# SM3320-BATT-EV.net
KiCad netlist of a schematic drawn in Altium Designer
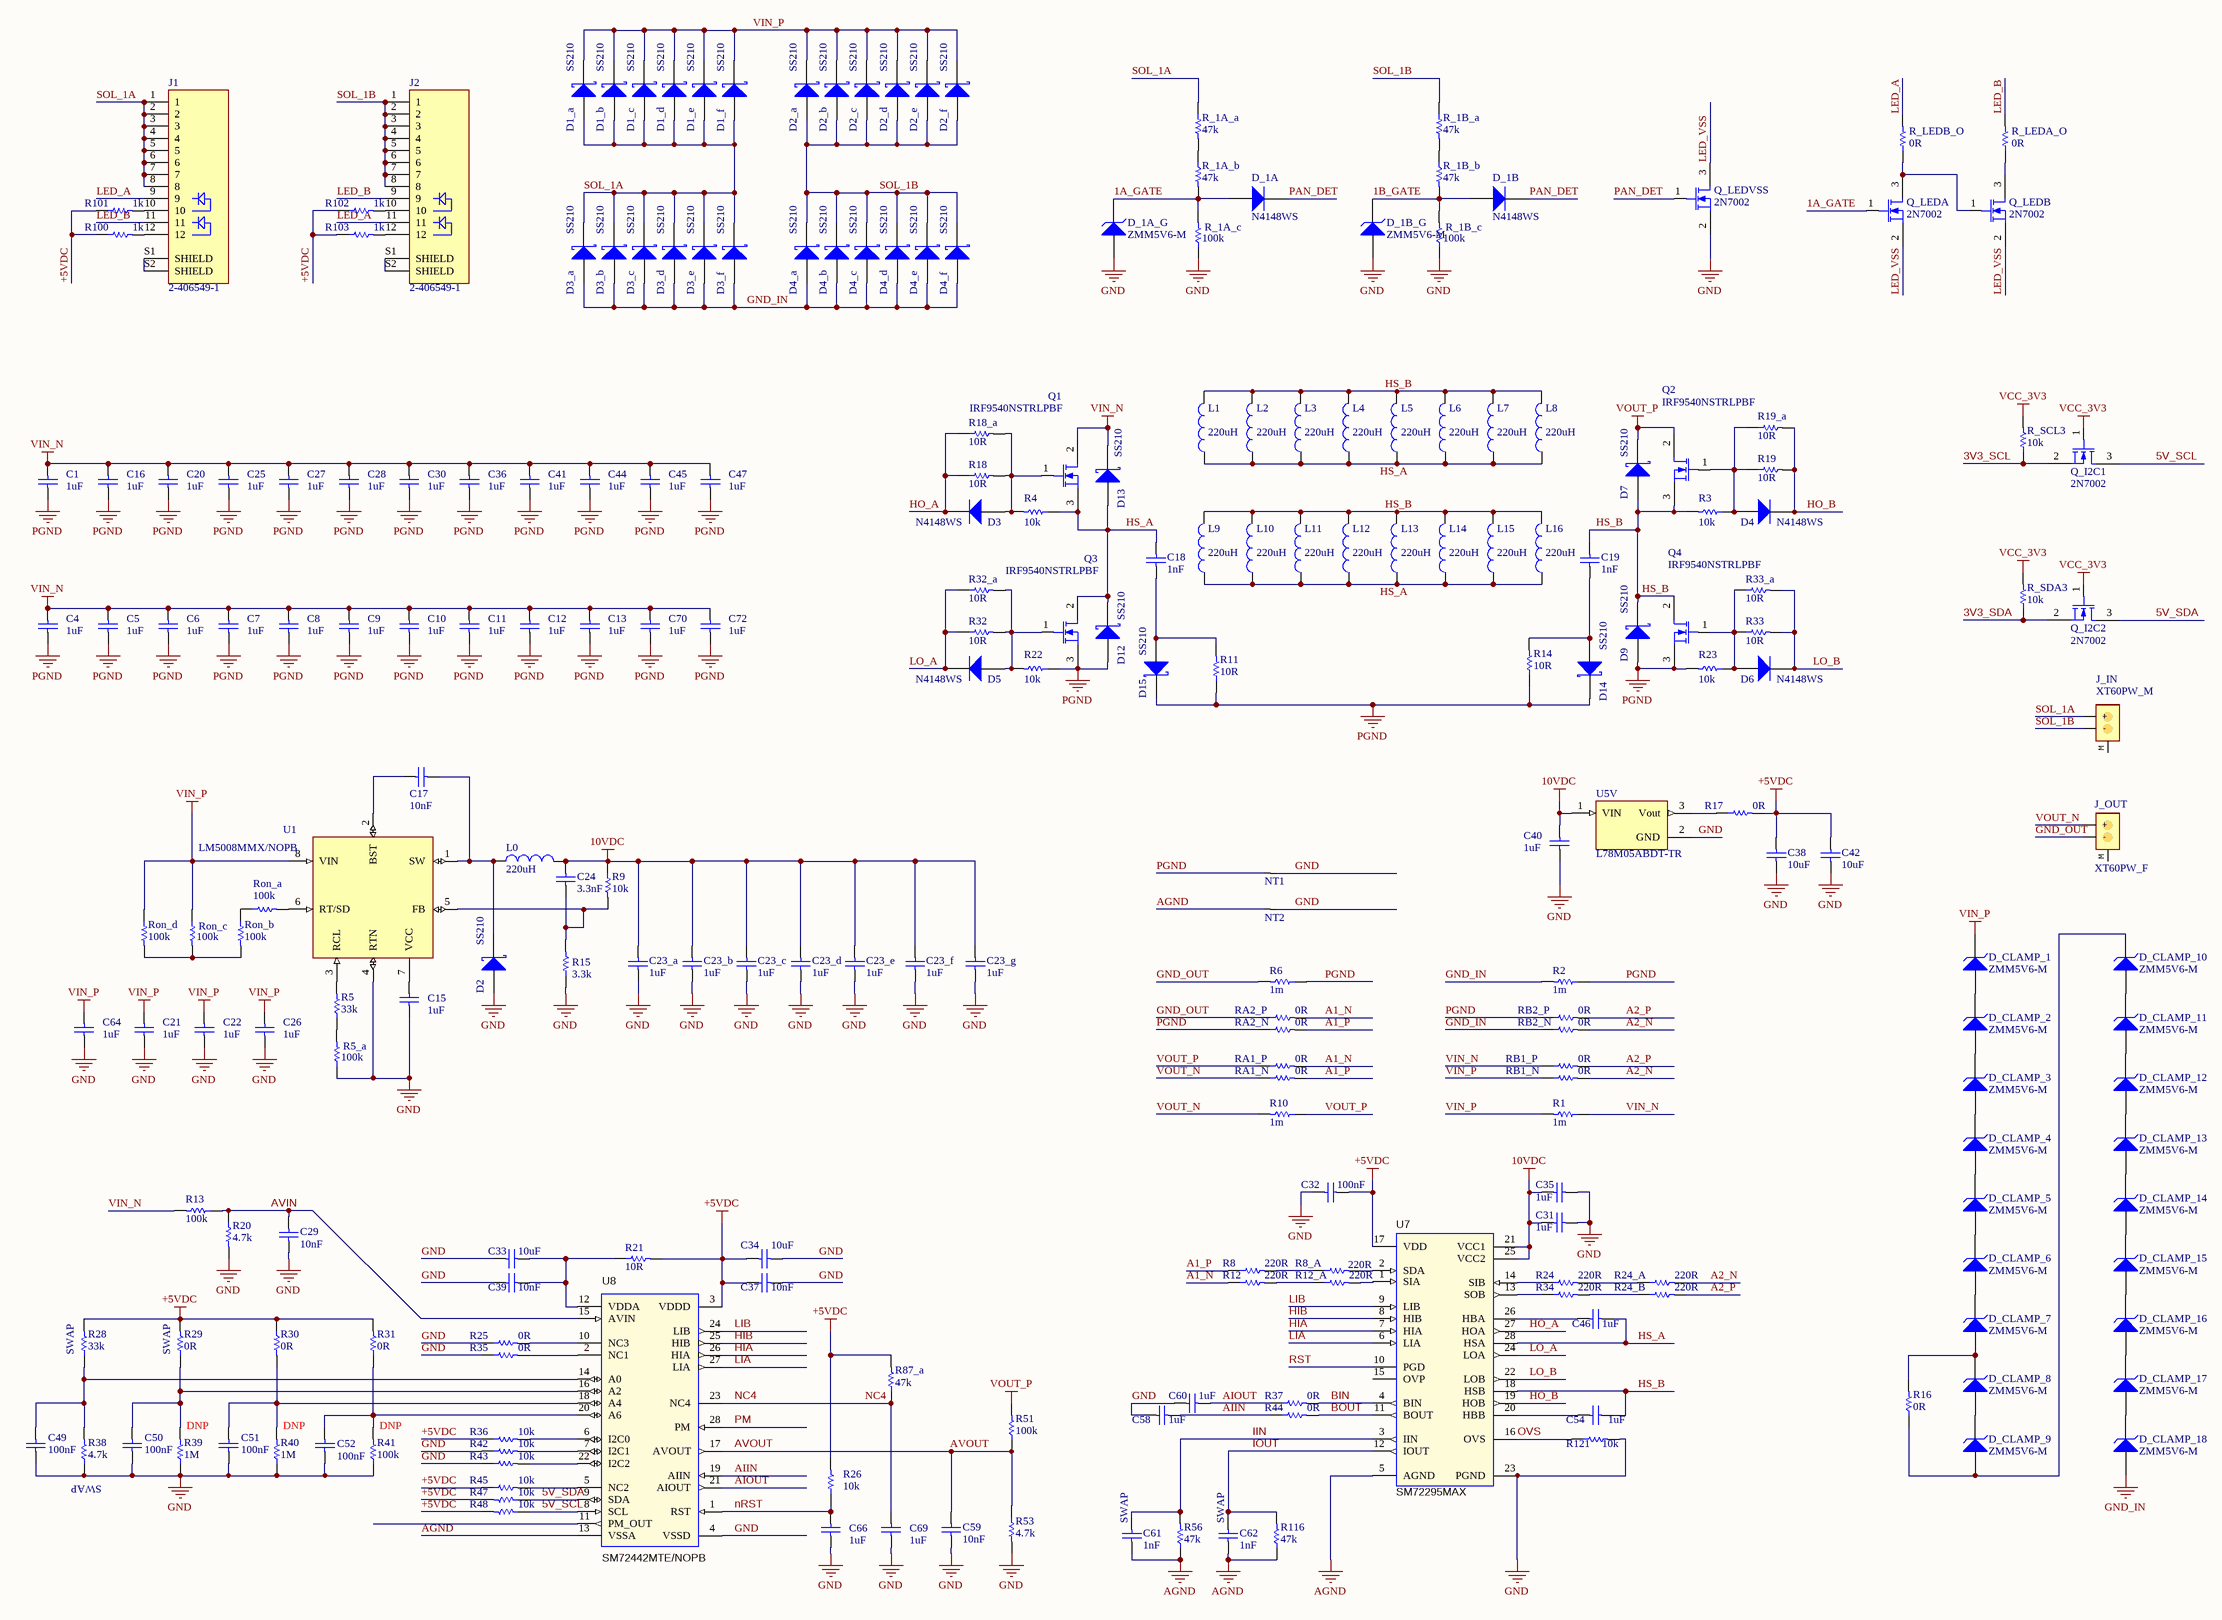
[diagram p0: SM3320-BATT-EV.SchDoc]

(export (version "E")
  (design (tool "Eeschema 10.0.6"))
  (components
    (comp (ref "C1")
      (value "1uF")
      (footprint "C_1206")
      (description "C - CAPACITOR - MLCC - 1uF - 100V - 1206 - X7R")
      (fields (field (name "LCSC PART #") "C91151") (field (name "Comment") "1206B105K101NT"))
      (libsource (lib "JLC_PCB") (part "1206B105K101NT"))
    )
    (comp (ref "C4")
      (value "1uF")
      (footprint "C_1206")
      (description "C - CAPACITOR - MLCC - 1uF - 100V - 1206 - X7R")
      (fields (field (name "LCSC PART #") "C91151") (field (name "Comment") "1206B105K101NT"))
      (libsource (lib "JLC_PCB") (part "1206B105K101NT"))
    )
    (comp (ref "C5")
      (value "1uF")
      (footprint "C_1206")
      (description "C - CAPACITOR - MLCC - 1uF - 100V - 1206 - X7R")
      (fields (field (name "LCSC PART #") "C91151") (field (name "Comment") "1206B105K101NT"))
      (libsource (lib "JLC_PCB") (part "1206B105K101NT"))
    )
    (comp (ref "C6")
      (value "1uF")
      (footprint "C_1206")
      (description "C - CAPACITOR - MLCC - 1uF - 100V - 1206 - X7R")
      (fields (field (name "LCSC PART #") "C91151") (field (name "Comment") "1206B105K101NT"))
      (libsource (lib "JLC_PCB") (part "1206B105K101NT"))
    )
    (comp (ref "C7")
      (value "1uF")
      (footprint "C_1206")
      (description "C - CAPACITOR - MLCC - 1uF - 100V - 1206 - X7R")
      (fields (field (name "LCSC PART #") "C91151") (field (name "Comment") "1206B105K101NT"))
      (libsource (lib "JLC_PCB") (part "1206B105K101NT"))
    )
    (comp (ref "C8")
      (value "1uF")
      (footprint "C_1206")
      (description "C - CAPACITOR - MLCC - 1uF - 100V - 1206 - X7R")
      (fields (field (name "LCSC PART #") "C91151") (field (name "Comment") "1206B105K101NT"))
      (libsource (lib "JLC_PCB") (part "1206B105K101NT"))
    )
    (comp (ref "C9")
      (value "1uF")
      (footprint "C_1206")
      (description "C - CAPACITOR - MLCC - 1uF - 100V - 1206 - X7R")
      (fields (field (name "LCSC PART #") "C91151") (field (name "Comment") "1206B105K101NT"))
      (libsource (lib "JLC_PCB") (part "1206B105K101NT"))
    )
    (comp (ref "C10")
      (value "1uF")
      (footprint "C_1206")
      (description "C - CAPACITOR - MLCC - 1uF - 100V - 1206 - X7R")
      (fields (field (name "LCSC PART #") "C91151") (field (name "Comment") "1206B105K101NT"))
      (libsource (lib "JLC_PCB") (part "1206B105K101NT"))
    )
    (comp (ref "C11")
      (value "1uF")
      (footprint "C_1206")
      (description "C - CAPACITOR - MLCC - 1uF - 100V - 1206 - X7R")
      (fields (field (name "LCSC PART #") "C91151") (field (name "Comment") "1206B105K101NT"))
      (libsource (lib "JLC_PCB") (part "1206B105K101NT"))
    )
    (comp (ref "C12")
      (value "1uF")
      (footprint "C_1206")
      (description "C - CAPACITOR - MLCC - 1uF - 100V - 1206 - X7R")
      (fields (field (name "LCSC PART #") "C91151") (field (name "Comment") "1206B105K101NT"))
      (libsource (lib "JLC_PCB") (part "1206B105K101NT"))
    )
    (comp (ref "C13")
      (value "1uF")
      (footprint "C_1206")
      (description "C - CAPACITOR - MLCC - 1uF - 100V - 1206 - X7R")
      (fields (field (name "LCSC PART #") "C91151") (field (name "Comment") "1206B105K101NT"))
      (libsource (lib "JLC_PCB") (part "1206B105K101NT"))
    )
    (comp (ref "C15")
      (value "1uF")
      (footprint "C_0402")
      (description "C - CAPACITOR - MLCC - 1uF - 25V - 0402")
      (fields (field (name "LCSC PART #") "C52923") (field (name "Comment") "CL05A105KA5NQNC"))
      (libsource (lib "JLC_PCB") (part "CL05A105KA5NQNC"))
    )
    (comp (ref "C16")
      (value "1uF")
      (footprint "C_1206")
      (description "C - CAPACITOR - MLCC - 1uF - 100V - 1206 - X7R")
      (fields (field (name "LCSC PART #") "C91151") (field (name "Comment") "1206B105K101NT"))
      (libsource (lib "JLC_PCB") (part "1206B105K101NT"))
    )
    (comp (ref "C17")
      (value "10nF")
      (footprint "C_0402")
      (description "C - CAPACITOR - MLCC - 10nF - 50V - 0402")
      (fields (field (name "LCSC PART #") "C15195") (field (name "Comment") "CL05B103KB5NNNC"))
      (libsource (lib "JLC_PCB") (part "CL05B103KB5NNNC"))
    )
    (comp (ref "C18")
      (value "1nF")
      (footprint "C_1206")
      (description "C - CAPACITOR - MLCC - 1nF - 2000V - 1206 - X7R")
      (fields (field (name "LCSC PART #") "C9196") (field (name "Comment") "1206B102K202NT"))
      (libsource (lib "JLC_PCB") (part "1206B102K202NT"))
    )
    (comp (ref "C19")
      (value "1nF")
      (footprint "C_1206")
      (description "C - CAPACITOR - MLCC - 1nF - 2000V - 1206 - X7R")
      (fields (field (name "LCSC PART #") "C9196") (field (name "Comment") "1206B102K202NT"))
      (libsource (lib "JLC_PCB") (part "1206B102K202NT"))
    )
    (comp (ref "C20")
      (value "1uF")
      (footprint "C_1206")
      (description "C - CAPACITOR - MLCC - 1uF - 100V - 1206 - X7R")
      (fields (field (name "LCSC PART #") "C91151") (field (name "Comment") "1206B105K101NT"))
      (libsource (lib "JLC_PCB") (part "1206B105K101NT"))
    )
    (comp (ref "C21")
      (value "1uF")
      (footprint "C_1206")
      (description "C - CAPACITOR - MLCC - 1uF - 100V - 1206 - X7R")
      (fields (field (name "LCSC PART #") "C91151") (field (name "Comment") "1206B105K101NT"))
      (libsource (lib "JLC_PCB") (part "1206B105K101NT"))
    )
    (comp (ref "C22")
      (value "1uF")
      (footprint "C_1206")
      (description "C - CAPACITOR - MLCC - 1uF - 100V - 1206 - X7R")
      (fields (field (name "LCSC PART #") "C91151") (field (name "Comment") "1206B105K101NT"))
      (libsource (lib "JLC_PCB") (part "1206B105K101NT"))
    )
    (comp (ref "C23_a")
      (value "1uF")
      (footprint "C_0402")
      (description "C - CAPACITOR - MLCC - 1uF - 25V - 0402")
      (fields (field (name "LCSC PART #") "C52923") (field (name "Comment") "CL05A105KA5NQNC"))
      (libsource (lib "JLC_PCB") (part "CL05A105KA5NQNC"))
    )
    (comp (ref "C23_b")
      (value "1uF")
      (footprint "C_0402")
      (description "C - CAPACITOR - MLCC - 1uF - 25V - 0402")
      (fields (field (name "LCSC PART #") "C52923") (field (name "Comment") "CL05A105KA5NQNC"))
      (libsource (lib "JLC_PCB") (part "CL05A105KA5NQNC"))
    )
    (comp (ref "C23_c")
      (value "1uF")
      (footprint "C_0402")
      (description "C - CAPACITOR - MLCC - 1uF - 25V - 0402")
      (fields (field (name "LCSC PART #") "C52923") (field (name "Comment") "CL05A105KA5NQNC"))
      (libsource (lib "JLC_PCB") (part "CL05A105KA5NQNC"))
    )
    (comp (ref "C23_d")
      (value "1uF")
      (footprint "C_0402")
      (description "C - CAPACITOR - MLCC - 1uF - 25V - 0402")
      (fields (field (name "LCSC PART #") "C52923") (field (name "Comment") "CL05A105KA5NQNC"))
      (libsource (lib "JLC_PCB") (part "CL05A105KA5NQNC"))
    )
    (comp (ref "C23_e")
      (value "1uF")
      (footprint "C_0402")
      (description "C - CAPACITOR - MLCC - 1uF - 25V - 0402")
      (fields (field (name "LCSC PART #") "C52923") (field (name "Comment") "CL05A105KA5NQNC"))
      (libsource (lib "JLC_PCB") (part "CL05A105KA5NQNC"))
    )
    (comp (ref "C23_f")
      (value "1uF")
      (footprint "C_0402")
      (description "C - CAPACITOR - MLCC - 1uF - 25V - 0402")
      (fields (field (name "LCSC PART #") "C52923") (field (name "Comment") "CL05A105KA5NQNC"))
      (libsource (lib "JLC_PCB") (part "CL05A105KA5NQNC"))
    )
    (comp (ref "C23_g")
      (value "1uF")
      (footprint "C_0402")
      (description "C - CAPACITOR - MLCC - 1uF - 25V - 0402")
      (fields (field (name "LCSC PART #") "C52923") (field (name "Comment") "CL05A105KA5NQNC"))
      (libsource (lib "JLC_PCB") (part "CL05A105KA5NQNC"))
    )
    (comp (ref "C24")
      (value "3.3nF")
      (footprint "C_0402")
      (description "C - CAPACITOR - MLCC - 3.3nF - 50V - 0402")
      (fields (field (name "LCSC PART #") "C26404") (field (name "Comment") "CL05B332KB5NNNC"))
      (libsource (lib "JLC_PCB") (part "CL05B332KB5NNNC"))
    )
    (comp (ref "C25")
      (value "1uF")
      (footprint "C_1206")
      (description "C - CAPACITOR - MLCC - 1uF - 100V - 1206 - X7R")
      (fields (field (name "LCSC PART #") "C91151") (field (name "Comment") "1206B105K101NT"))
      (libsource (lib "JLC_PCB") (part "1206B105K101NT"))
    )
    (comp (ref "C26")
      (value "1uF")
      (footprint "C_1206")
      (description "C - CAPACITOR - MLCC - 1uF - 100V - 1206 - X7R")
      (fields (field (name "LCSC PART #") "C91151") (field (name "Comment") "1206B105K101NT"))
      (libsource (lib "JLC_PCB") (part "1206B105K101NT"))
    )
    (comp (ref "C27")
      (value "1uF")
      (footprint "C_1206")
      (description "C - CAPACITOR - MLCC - 1uF - 100V - 1206 - X7R")
      (fields (field (name "LCSC PART #") "C91151") (field (name "Comment") "1206B105K101NT"))
      (libsource (lib "JLC_PCB") (part "1206B105K101NT"))
    )
    (comp (ref "C28")
      (value "1uF")
      (footprint "C_1206")
      (description "C - CAPACITOR - MLCC - 1uF - 100V - 1206 - X7R")
      (fields (field (name "LCSC PART #") "C91151") (field (name "Comment") "1206B105K101NT"))
      (libsource (lib "JLC_PCB") (part "1206B105K101NT"))
    )
    (comp (ref "C29")
      (value "10nF")
      (footprint "C_0402")
      (description "C - CAPACITOR - MLCC - 10nF - 50V - 0402")
      (fields (field (name "LCSC PART #") "C15195") (field (name "Comment") "CL05B103KB5NNNC"))
      (libsource (lib "JLC_PCB") (part "CL05B103KB5NNNC"))
    )
    (comp (ref "C30")
      (value "1uF")
      (footprint "C_1206")
      (description "C - CAPACITOR - MLCC - 1uF - 100V - 1206 - X7R")
      (fields (field (name "LCSC PART #") "C91151") (field (name "Comment") "1206B105K101NT"))
      (libsource (lib "JLC_PCB") (part "1206B105K101NT"))
    )
    (comp (ref "C31")
      (value "1uF")
      (footprint "C_0402")
      (description "C - CAPACITOR - MLCC - 1uF - 25V - 0402")
      (fields (field (name "LCSC PART #") "C52923") (field (name "Comment") "CL05A105KA5NQNC"))
      (libsource (lib "JLC_PCB") (part "CL05A105KA5NQNC"))
    )
    (comp (ref "C32")
      (value "100nF")
      (footprint "C_0402")
      (description "C - CAPACITOR - MLCC - 100nF - 16V - 0402")
      (fields (field (name "LCSC PART #") "C1525") (field (name "Comment") "CL05B104KO5NNNC"))
      (libsource (lib "JLC_PCB") (part "CL05B104KO5NNNC"))
    )
    (comp (ref "C33")
      (value "10uF")
      (footprint "C_0402")
      (description "C - CAPACITOR - MLCC - 10uF - 6.3V - 0402")
      (fields (field (name "LCSC PART #") "C15525") (field (name "Comment") "CL05A106MQ5NUNC"))
      (libsource (lib "JLC_PCB") (part "CL05A106MQ5NUNC"))
    )
    (comp (ref "C34")
      (value "10uF")
      (footprint "C_0402")
      (description "C - CAPACITOR - MLCC - 10uF - 6.3V - 0402")
      (fields (field (name "LCSC PART #") "C15525") (field (name "Comment") "CL05A106MQ5NUNC"))
      (libsource (lib "JLC_PCB") (part "CL05A106MQ5NUNC"))
    )
    (comp (ref "C35")
      (value "1uF")
      (footprint "C_0402")
      (description "C - CAPACITOR - MLCC - 1uF - 25V - 0402")
      (fields (field (name "LCSC PART #") "C52923") (field (name "Comment") "CL05A105KA5NQNC"))
      (libsource (lib "JLC_PCB") (part "CL05A105KA5NQNC"))
    )
    (comp (ref "C36")
      (value "1uF")
      (footprint "C_1206")
      (description "C - CAPACITOR - MLCC - 1uF - 100V - 1206 - X7R")
      (fields (field (name "LCSC PART #") "C91151") (field (name "Comment") "1206B105K101NT"))
      (libsource (lib "JLC_PCB") (part "1206B105K101NT"))
    )
    (comp (ref "C37")
      (value "10nF")
      (footprint "C_0402")
      (description "C - CAPACITOR - MLCC - 10nF - 50V - 0402")
      (fields (field (name "LCSC PART #") "C15195") (field (name "Comment") "CL05B103KB5NNNC"))
      (libsource (lib "JLC_PCB") (part "CL05B103KB5NNNC"))
    )
    (comp (ref "C38")
      (value "10uF")
      (footprint "C_0402")
      (description "C - CAPACITOR - MLCC - 10uF - 6.3V - 0402")
      (fields (field (name "LCSC PART #") "C15525") (field (name "Comment") "CL05A106MQ5NUNC"))
      (libsource (lib "JLC_PCB") (part "CL05A106MQ5NUNC"))
    )
    (comp (ref "C39")
      (value "10nF")
      (footprint "C_0402")
      (description "C - CAPACITOR - MLCC - 10nF - 50V - 0402")
      (fields (field (name "LCSC PART #") "C15195") (field (name "Comment") "CL05B103KB5NNNC"))
      (libsource (lib "JLC_PCB") (part "CL05B103KB5NNNC"))
    )
    (comp (ref "C40")
      (value "1uF")
      (footprint "C_0402")
      (description "C - CAPACITOR - MLCC - 1uF - 25V - 0402")
      (fields (field (name "LCSC PART #") "C52923") (field (name "Comment") "CL05A105KA5NQNC"))
      (libsource (lib "JLC_PCB") (part "CL05A105KA5NQNC"))
    )
    (comp (ref "C41")
      (value "1uF")
      (footprint "C_1206")
      (description "C - CAPACITOR - MLCC - 1uF - 100V - 1206 - X7R")
      (fields (field (name "LCSC PART #") "C91151") (field (name "Comment") "1206B105K101NT"))
      (libsource (lib "JLC_PCB") (part "1206B105K101NT"))
    )
    (comp (ref "C42")
      (value "10uF")
      (footprint "C_0402")
      (description "C - CAPACITOR - MLCC - 10uF - 6.3V - 0402")
      (fields (field (name "LCSC PART #") "C15525") (field (name "Comment") "CL05A106MQ5NUNC"))
      (libsource (lib "JLC_PCB") (part "CL05A106MQ5NUNC"))
    )
    (comp (ref "C44")
      (value "1uF")
      (footprint "C_1206")
      (description "C - CAPACITOR - MLCC - 1uF - 100V - 1206 - X7R")
      (fields (field (name "LCSC PART #") "C91151") (field (name "Comment") "1206B105K101NT"))
      (libsource (lib "JLC_PCB") (part "1206B105K101NT"))
    )
    (comp (ref "C45")
      (value "1uF")
      (footprint "C_1206")
      (description "C - CAPACITOR - MLCC - 1uF - 100V - 1206 - X7R")
      (fields (field (name "LCSC PART #") "C91151") (field (name "Comment") "1206B105K101NT"))
      (libsource (lib "JLC_PCB") (part "1206B105K101NT"))
    )
    (comp (ref "C46")
      (value "1uF")
      (footprint "C_0402")
      (description "C - CAPACITOR - MLCC - 1uF - 25V - 0402")
      (fields (field (name "LCSC PART #") "C52923") (field (name "Comment") "CL05A105KA5NQNC"))
      (libsource (lib "JLC_PCB") (part "CL05A105KA5NQNC"))
    )
    (comp (ref "C47")
      (value "1uF")
      (footprint "C_1206")
      (description "C - CAPACITOR - MLCC - 1uF - 100V - 1206 - X7R")
      (fields (field (name "LCSC PART #") "C91151") (field (name "Comment") "1206B105K101NT"))
      (libsource (lib "JLC_PCB") (part "1206B105K101NT"))
    )
    (comp (ref "C49")
      (value "100nF")
      (footprint "C_0402")
      (description "C - CAPACITOR - MLCC - 100nF - 16V - 0402")
      (fields (field (name "LCSC PART #") "C1525") (field (name "Comment") "CL05B104KO5NNNC"))
      (libsource (lib "JLC_PCB") (part "CL05B104KO5NNNC"))
    )
    (comp (ref "C50")
      (value "100nF")
      (footprint "C_0402")
      (description "C - CAPACITOR - MLCC - 100nF - 16V - 0402")
      (fields (field (name "LCSC PART #") "C1525") (field (name "Comment") "CL05B104KO5NNNC"))
      (libsource (lib "JLC_PCB") (part "CL05B104KO5NNNC"))
    )
    (comp (ref "C51")
      (value "100nF")
      (footprint "C_0402")
      (description "C - CAPACITOR - MLCC - 100nF - 16V - 0402")
      (fields (field (name "LCSC PART #") "C1525") (field (name "Comment") "CL05B104KO5NNNC"))
      (libsource (lib "JLC_PCB") (part "CL05B104KO5NNNC"))
    )
    (comp (ref "C52")
      (value "100nF")
      (footprint "C_0402")
      (description "C - CAPACITOR - MLCC - 100nF - 16V - 0402")
      (fields (field (name "LCSC PART #") "C1525") (field (name "Comment") "CL05B104KO5NNNC"))
      (libsource (lib "JLC_PCB") (part "CL05B104KO5NNNC"))
    )
    (comp (ref "C54")
      (value "1uF")
      (footprint "C_0402")
      (description "C - CAPACITOR - MLCC - 1uF - 25V - 0402")
      (fields (field (name "LCSC PART #") "C52923") (field (name "Comment") "CL05A105KA5NQNC"))
      (libsource (lib "JLC_PCB") (part "CL05A105KA5NQNC"))
    )
    (comp (ref "C58")
      (value "1uF")
      (footprint "C_0402")
      (description "C - CAPACITOR - MLCC - 1uF - 25V - 0402")
      (fields (field (name "LCSC PART #") "C52923") (field (name "Comment") "CL05A105KA5NQNC"))
      (libsource (lib "JLC_PCB") (part "CL05A105KA5NQNC"))
    )
    (comp (ref "C59")
      (value "10nF")
      (footprint "C_0402")
      (description "C - CAPACITOR - MLCC - 10nF - 50V - 0402")
      (fields (field (name "LCSC PART #") "C15195") (field (name "Comment") "CL05B103KB5NNNC"))
      (libsource (lib "JLC_PCB") (part "CL05B103KB5NNNC"))
    )
    (comp (ref "C60")
      (value "1uF")
      (footprint "C_0402")
      (description "C - CAPACITOR - MLCC - 1uF - 25V - 0402")
      (fields (field (name "LCSC PART #") "C52923") (field (name "Comment") "CL05A105KA5NQNC"))
      (libsource (lib "JLC_PCB") (part "CL05A105KA5NQNC"))
    )
    (comp (ref "C61")
      (value "1nF")
      (footprint "C_0402")
      (description "C - CAPACITOR - MLCC - 1nF - 50V - 0402")
      (fields (field (name "LCSC PART #") "C1523") (field (name "Comment") "0402B102K500NT"))
      (libsource (lib "JLC_PCB") (part "0402B102K500NT"))
    )
    (comp (ref "C62")
      (value "1nF")
      (footprint "C_0402")
      (description "C - CAPACITOR - MLCC - 1nF - 50V - 0402")
      (fields (field (name "LCSC PART #") "C1523") (field (name "Comment") "0402B102K500NT"))
      (libsource (lib "JLC_PCB") (part "0402B102K500NT"))
    )
    (comp (ref "C64")
      (value "1uF")
      (footprint "C_1206")
      (description "C - CAPACITOR - MLCC - 1uF - 100V - 1206 - X7R")
      (fields (field (name "LCSC PART #") "C91151") (field (name "Comment") "1206B105K101NT"))
      (libsource (lib "JLC_PCB") (part "1206B105K101NT"))
    )
    (comp (ref "C66")
      (value "1uF")
      (footprint "C_0402")
      (description "C - CAPACITOR - MLCC - 1uF - 25V - 0402")
      (fields (field (name "LCSC PART #") "C52923") (field (name "Comment") "CL05A105KA5NQNC"))
      (libsource (lib "JLC_PCB") (part "CL05A105KA5NQNC"))
    )
    (comp (ref "C69")
      (value "1uF")
      (footprint "C_0402")
      (description "C - CAPACITOR - MLCC - 1uF - 25V - 0402")
      (fields (field (name "LCSC PART #") "C52923") (field (name "Comment") "CL05A105KA5NQNC"))
      (libsource (lib "JLC_PCB") (part "CL05A105KA5NQNC"))
    )
    (comp (ref "C70")
      (value "1uF")
      (footprint "C_1206")
      (description "C - CAPACITOR - MLCC - 1uF - 100V - 1206 - X7R")
      (fields (field (name "LCSC PART #") "C91151") (field (name "Comment") "1206B105K101NT"))
      (libsource (lib "JLC_PCB") (part "1206B105K101NT"))
    )
    (comp (ref "C72")
      (value "1uF")
      (footprint "C_1206")
      (description "C - CAPACITOR - MLCC - 1uF - 100V - 1206 - X7R")
      (fields (field (name "LCSC PART #") "C91151") (field (name "Comment") "1206B105K101NT"))
      (libsource (lib "JLC_PCB") (part "1206B105K101NT"))
    )
    (comp (ref "D1_a")
      (value "SS210")
      (footprint "DO-214AC")
      (description "D - DIODE - SCHOTTKY - 100V - 2A")
      (fields (field (name "LCSC PART #") "C14996"))
      (libsource (lib "JLC_PCB") (part "SS210"))
    )
    (comp (ref "D1_b")
      (value "SS210")
      (footprint "DO-214AC")
      (description "D - DIODE - SCHOTTKY - 100V - 2A")
      (fields (field (name "LCSC PART #") "C14996"))
      (libsource (lib "JLC_PCB") (part "SS210"))
    )
    (comp (ref "D1_c")
      (value "SS210")
      (footprint "DO-214AC")
      (description "D - DIODE - SCHOTTKY - 100V - 2A")
      (fields (field (name "LCSC PART #") "C14996"))
      (libsource (lib "JLC_PCB") (part "SS210"))
    )
    (comp (ref "D1_d")
      (value "SS210")
      (footprint "DO-214AC")
      (description "D - DIODE - SCHOTTKY - 100V - 2A")
      (fields (field (name "LCSC PART #") "C14996"))
      (libsource (lib "JLC_PCB") (part "SS210"))
    )
    (comp (ref "D1_e")
      (value "SS210")
      (footprint "DO-214AC")
      (description "D - DIODE - SCHOTTKY - 100V - 2A")
      (fields (field (name "LCSC PART #") "C14996"))
      (libsource (lib "JLC_PCB") (part "SS210"))
    )
    (comp (ref "D1_f")
      (value "SS210")
      (footprint "DO-214AC")
      (description "D - DIODE - SCHOTTKY - 100V - 2A")
      (fields (field (name "LCSC PART #") "C14996"))
      (libsource (lib "JLC_PCB") (part "SS210"))
    )
    (comp (ref "D2")
      (value "SS210")
      (footprint "DO-214AC")
      (description "D - DIODE - SCHOTTKY - 100V - 2A")
      (fields (field (name "LCSC PART #") "C14996"))
      (libsource (lib "JLC_PCB") (part "SS210"))
    )
    (comp (ref "D2_a")
      (value "SS210")
      (footprint "DO-214AC")
      (description "D - DIODE - SCHOTTKY - 100V - 2A")
      (fields (field (name "LCSC PART #") "C14996"))
      (libsource (lib "JLC_PCB") (part "SS210"))
    )
    (comp (ref "D2_b")
      (value "SS210")
      (footprint "DO-214AC")
      (description "D - DIODE - SCHOTTKY - 100V - 2A")
      (fields (field (name "LCSC PART #") "C14996"))
      (libsource (lib "JLC_PCB") (part "SS210"))
    )
    (comp (ref "D2_c")
      (value "SS210")
      (footprint "DO-214AC")
      (description "D - DIODE - SCHOTTKY - 100V - 2A")
      (fields (field (name "LCSC PART #") "C14996"))
      (libsource (lib "JLC_PCB") (part "SS210"))
    )
    (comp (ref "D2_d")
      (value "SS210")
      (footprint "DO-214AC")
      (description "D - DIODE - SCHOTTKY - 100V - 2A")
      (fields (field (name "LCSC PART #") "C14996"))
      (libsource (lib "JLC_PCB") (part "SS210"))
    )
    (comp (ref "D2_e")
      (value "SS210")
      (footprint "DO-214AC")
      (description "D - DIODE - SCHOTTKY - 100V - 2A")
      (fields (field (name "LCSC PART #") "C14996"))
      (libsource (lib "JLC_PCB") (part "SS210"))
    )
    (comp (ref "D2_f")
      (value "SS210")
      (footprint "DO-214AC")
      (description "D - DIODE - SCHOTTKY - 100V - 2A")
      (fields (field (name "LCSC PART #") "C14996"))
      (libsource (lib "JLC_PCB") (part "SS210"))
    )
    (comp (ref "D3")
      (value "N4148WS")
      (footprint "SOD-323")
      (description "D - DIODE - FAST TRR - 100V - 150mA - 4ns")
      (fields (field (name "LCSC PART #") "C2128"))
      (libsource (lib "JLC_PCB") (part "N4148WS"))
    )
    (comp (ref "D3_a")
      (value "SS210")
      (footprint "DO-214AC")
      (description "D - DIODE - SCHOTTKY - 100V - 2A")
      (fields (field (name "LCSC PART #") "C14996"))
      (libsource (lib "JLC_PCB") (part "SS210"))
    )
    (comp (ref "D3_b")
      (value "SS210")
      (footprint "DO-214AC")
      (description "D - DIODE - SCHOTTKY - 100V - 2A")
      (fields (field (name "LCSC PART #") "C14996"))
      (libsource (lib "JLC_PCB") (part "SS210"))
    )
    (comp (ref "D3_c")
      (value "SS210")
      (footprint "DO-214AC")
      (description "D - DIODE - SCHOTTKY - 100V - 2A")
      (fields (field (name "LCSC PART #") "C14996"))
      (libsource (lib "JLC_PCB") (part "SS210"))
    )
    (comp (ref "D3_d")
      (value "SS210")
      (footprint "DO-214AC")
      (description "D - DIODE - SCHOTTKY - 100V - 2A")
      (fields (field (name "LCSC PART #") "C14996"))
      (libsource (lib "JLC_PCB") (part "SS210"))
    )
    (comp (ref "D3_e")
      (value "SS210")
      (footprint "DO-214AC")
      (description "D - DIODE - SCHOTTKY - 100V - 2A")
      (fields (field (name "LCSC PART #") "C14996"))
      (libsource (lib "JLC_PCB") (part "SS210"))
    )
    (comp (ref "D3_f")
      (value "SS210")
      (footprint "DO-214AC")
      (description "D - DIODE - SCHOTTKY - 100V - 2A")
      (fields (field (name "LCSC PART #") "C14996"))
      (libsource (lib "JLC_PCB") (part "SS210"))
    )
    (comp (ref "D4")
      (value "N4148WS")
      (footprint "SOD-323")
      (description "D - DIODE - FAST TRR - 100V - 150mA - 4ns")
      (fields (field (name "LCSC PART #") "C2128"))
      (libsource (lib "JLC_PCB") (part "N4148WS"))
    )
    (comp (ref "D4_a")
      (value "SS210")
      (footprint "DO-214AC")
      (description "D - DIODE - SCHOTTKY - 100V - 2A")
      (fields (field (name "LCSC PART #") "C14996"))
      (libsource (lib "JLC_PCB") (part "SS210"))
    )
    (comp (ref "D4_b")
      (value "SS210")
      (footprint "DO-214AC")
      (description "D - DIODE - SCHOTTKY - 100V - 2A")
      (fields (field (name "LCSC PART #") "C14996"))
      (libsource (lib "JLC_PCB") (part "SS210"))
    )
    (comp (ref "D4_c")
      (value "SS210")
      (footprint "DO-214AC")
      (description "D - DIODE - SCHOTTKY - 100V - 2A")
      (fields (field (name "LCSC PART #") "C14996"))
      (libsource (lib "JLC_PCB") (part "SS210"))
    )
    (comp (ref "D4_d")
      (value "SS210")
      (footprint "DO-214AC")
      (description "D - DIODE - SCHOTTKY - 100V - 2A")
      (fields (field (name "LCSC PART #") "C14996"))
      (libsource (lib "JLC_PCB") (part "SS210"))
    )
    (comp (ref "D4_e")
      (value "SS210")
      (footprint "DO-214AC")
      (description "D - DIODE - SCHOTTKY - 100V - 2A")
      (fields (field (name "LCSC PART #") "C14996"))
      (libsource (lib "JLC_PCB") (part "SS210"))
    )
    (comp (ref "D4_f")
      (value "SS210")
      (footprint "DO-214AC")
      (description "D - DIODE - SCHOTTKY - 100V - 2A")
      (fields (field (name "LCSC PART #") "C14996"))
      (libsource (lib "JLC_PCB") (part "SS210"))
    )
    (comp (ref "D5")
      (value "N4148WS")
      (footprint "SOD-323")
      (description "D - DIODE - FAST TRR - 100V - 150mA - 4ns")
      (fields (field (name "LCSC PART #") "C2128"))
      (libsource (lib "JLC_PCB") (part "N4148WS"))
    )
    (comp (ref "D6")
      (value "N4148WS")
      (footprint "SOD-323")
      (description "D - DIODE - FAST TRR - 100V - 150mA - 4ns")
      (fields (field (name "LCSC PART #") "C2128"))
      (libsource (lib "JLC_PCB") (part "N4148WS"))
    )
    (comp (ref "D7")
      (value "SS210")
      (footprint "DO-214AC")
      (description "D - DIODE - SCHOTTKY - 100V - 2A")
      (fields (field (name "LCSC PART #") "C14996"))
      (libsource (lib "JLC_PCB") (part "SS210"))
    )
    (comp (ref "D9")
      (value "SS210")
      (footprint "DO-214AC")
      (description "D - DIODE - SCHOTTKY - 100V - 2A")
      (fields (field (name "LCSC PART #") "C14996"))
      (libsource (lib "JLC_PCB") (part "SS210"))
    )
    (comp (ref "D12")
      (value "SS210")
      (footprint "DO-214AC")
      (description "D - DIODE - SCHOTTKY - 100V - 2A")
      (fields (field (name "LCSC PART #") "C14996"))
      (libsource (lib "JLC_PCB") (part "SS210"))
    )
    (comp (ref "D13")
      (value "SS210")
      (footprint "DO-214AC")
      (description "D - DIODE - SCHOTTKY - 100V - 2A")
      (fields (field (name "LCSC PART #") "C14996"))
      (libsource (lib "JLC_PCB") (part "SS210"))
    )
    (comp (ref "D14")
      (value "SS210")
      (footprint "DO-214AC")
      (description "D - DIODE - SCHOTTKY - 100V - 2A")
      (fields (field (name "LCSC PART #") "C14996"))
      (libsource (lib "JLC_PCB") (part "SS210"))
    )
    (comp (ref "D15")
      (value "SS210")
      (footprint "DO-214AC")
      (description "D - DIODE - SCHOTTKY - 100V - 2A")
      (fields (field (name "LCSC PART #") "C14996"))
      (libsource (lib "JLC_PCB") (part "SS210"))
    )
    (comp (ref "D_1A")
      (value "N4148WS")
      (footprint "SOD-323")
      (description "D - DIODE - FAST TRR - 100V - 150mA - 4ns")
      (fields (field (name "LCSC PART #") "C2128"))
      (libsource (lib "JLC_PCB") (part "N4148WS"))
    )
    (comp (ref "D_1A_G")
      (value "ZMM5V6-M")
      (footprint "DO-213AA")
      (description "D - DIODE - ZENER - 5.6V - 500mW")
      (fields (field (name "LCSC PART #") "C8062"))
      (libsource (lib "JLC_PCB") (part "ZMM5V6-M"))
    )
    (comp (ref "D_1B")
      (value "N4148WS")
      (footprint "SOD-323")
      (description "D - DIODE - FAST TRR - 100V - 150mA - 4ns")
      (fields (field (name "LCSC PART #") "C2128"))
      (libsource (lib "JLC_PCB") (part "N4148WS"))
    )
    (comp (ref "D_1B_G")
      (value "ZMM5V6-M")
      (footprint "DO-213AA")
      (description "D - DIODE - ZENER - 5.6V - 500mW")
      (fields (field (name "LCSC PART #") "C8062"))
      (libsource (lib "JLC_PCB") (part "ZMM5V6-M"))
    )
    (comp (ref "D_CLAMP_1")
      (value "ZMM5V6-M")
      (footprint "DO-213AA")
      (description "D - DIODE - ZENER - 5.6V - 500mW")
      (fields (field (name "LCSC PART #") "C8062"))
      (libsource (lib "JLC_PCB") (part "ZMM5V6-M"))
    )
    (comp (ref "D_CLAMP_2")
      (value "ZMM5V6-M")
      (footprint "DO-213AA")
      (description "D - DIODE - ZENER - 5.6V - 500mW")
      (fields (field (name "LCSC PART #") "C8062"))
      (libsource (lib "JLC_PCB") (part "ZMM5V6-M"))
    )
    (comp (ref "D_CLAMP_3")
      (value "ZMM5V6-M")
      (footprint "DO-213AA")
      (description "D - DIODE - ZENER - 5.6V - 500mW")
      (fields (field (name "LCSC PART #") "C8062"))
      (libsource (lib "JLC_PCB") (part "ZMM5V6-M"))
    )
    (comp (ref "D_CLAMP_4")
      (value "ZMM5V6-M")
      (footprint "DO-213AA")
      (description "D - DIODE - ZENER - 5.6V - 500mW")
      (fields (field (name "LCSC PART #") "C8062"))
      (libsource (lib "JLC_PCB") (part "ZMM5V6-M"))
    )
    (comp (ref "D_CLAMP_5")
      (value "ZMM5V6-M")
      (footprint "DO-213AA")
      (description "D - DIODE - ZENER - 5.6V - 500mW")
      (fields (field (name "LCSC PART #") "C8062"))
      (libsource (lib "JLC_PCB") (part "ZMM5V6-M"))
    )
    (comp (ref "D_CLAMP_6")
      (value "ZMM5V6-M")
      (footprint "DO-213AA")
      (description "D - DIODE - ZENER - 5.6V - 500mW")
      (fields (field (name "LCSC PART #") "C8062"))
      (libsource (lib "JLC_PCB") (part "ZMM5V6-M"))
    )
    (comp (ref "D_CLAMP_7")
      (value "ZMM5V6-M")
      (footprint "DO-213AA")
      (description "D - DIODE - ZENER - 5.6V - 500mW")
      (fields (field (name "LCSC PART #") "C8062"))
      (libsource (lib "JLC_PCB") (part "ZMM5V6-M"))
    )
    (comp (ref "D_CLAMP_8")
      (value "ZMM5V6-M")
      (footprint "DO-213AA")
      (description "D - DIODE - ZENER - 5.6V - 500mW")
      (fields (field (name "LCSC PART #") "C8062"))
      (libsource (lib "JLC_PCB") (part "ZMM5V6-M"))
    )
    (comp (ref "D_CLAMP_9")
      (value "ZMM5V6-M")
      (footprint "DO-213AA")
      (description "D - DIODE - ZENER - 5.6V - 500mW")
      (fields (field (name "LCSC PART #") "C8062"))
      (libsource (lib "JLC_PCB") (part "ZMM5V6-M"))
    )
    (comp (ref "D_CLAMP_10")
      (value "ZMM5V6-M")
      (footprint "DO-213AA")
      (description "D - DIODE - ZENER - 5.6V - 500mW")
      (fields (field (name "LCSC PART #") "C8062"))
      (libsource (lib "JLC_PCB") (part "ZMM5V6-M"))
    )
    (comp (ref "D_CLAMP_11")
      (value "ZMM5V6-M")
      (footprint "DO-213AA")
      (description "D - DIODE - ZENER - 5.6V - 500mW")
      (fields (field (name "LCSC PART #") "C8062"))
      (libsource (lib "JLC_PCB") (part "ZMM5V6-M"))
    )
    (comp (ref "D_CLAMP_12")
      (value "ZMM5V6-M")
      (footprint "DO-213AA")
      (description "D - DIODE - ZENER - 5.6V - 500mW")
      (fields (field (name "LCSC PART #") "C8062"))
      (libsource (lib "JLC_PCB") (part "ZMM5V6-M"))
    )
    (comp (ref "D_CLAMP_13")
      (value "ZMM5V6-M")
      (footprint "DO-213AA")
      (description "D - DIODE - ZENER - 5.6V - 500mW")
      (fields (field (name "LCSC PART #") "C8062"))
      (libsource (lib "JLC_PCB") (part "ZMM5V6-M"))
    )
    (comp (ref "D_CLAMP_14")
      (value "ZMM5V6-M")
      (footprint "DO-213AA")
      (description "D - DIODE - ZENER - 5.6V - 500mW")
      (fields (field (name "LCSC PART #") "C8062"))
      (libsource (lib "JLC_PCB") (part "ZMM5V6-M"))
    )
    (comp (ref "D_CLAMP_15")
      (value "ZMM5V6-M")
      (footprint "DO-213AA")
      (description "D - DIODE - ZENER - 5.6V - 500mW")
      (fields (field (name "LCSC PART #") "C8062"))
      (libsource (lib "JLC_PCB") (part "ZMM5V6-M"))
    )
    (comp (ref "D_CLAMP_16")
      (value "ZMM5V6-M")
      (footprint "DO-213AA")
      (description "D - DIODE - ZENER - 5.6V - 500mW")
      (fields (field (name "LCSC PART #") "C8062"))
      (libsource (lib "JLC_PCB") (part "ZMM5V6-M"))
    )
    (comp (ref "D_CLAMP_17")
      (value "ZMM5V6-M")
      (footprint "DO-213AA")
      (description "D - DIODE - ZENER - 5.6V - 500mW")
      (fields (field (name "LCSC PART #") "C8062"))
      (libsource (lib "JLC_PCB") (part "ZMM5V6-M"))
    )
    (comp (ref "D_CLAMP_18")
      (value "ZMM5V6-M")
      (footprint "DO-213AA")
      (description "D - DIODE - ZENER - 5.6V - 500mW")
      (fields (field (name "LCSC PART #") "C8062"))
      (libsource (lib "JLC_PCB") (part "ZMM5V6-M"))
    )
    (comp (ref "J1")
      (value "2-406549-1")
      (footprint "TE_2-406549-1")
      (description "J - JACK - ETHERNET - Right - THT")
      (fields (field (name "LCSC PART #") "C125068"))
      (libsource (lib "JLC_PCB") (part "2-406549-1"))
    )
    (comp (ref "J2")
      (value "2-406549-1")
      (footprint "TE_2-406549-1")
      (description "J - JACK - ETHERNET - Right - THT")
      (fields (field (name "LCSC PART #") "C125068"))
      (libsource (lib "JLC_PCB") (part "2-406549-1"))
    )
    (comp (ref "J_IN")
      (value "XT60PW_M")
      (footprint "XT60PW_M")
      (description "J - JACK - POWER - XT60 - RIGHT - MALE")
      (fields (field (name "LCSC PART #") "X"))
      (libsource (lib "JLC_PCB") (part "XT60PW_M"))
    )
    (comp (ref "J_OUT")
      (value "XT60PW_F")
      (footprint "XT60PW_F")
      (description "J - JACK - POWER - XT60 - RIGHT - FEMALE")
      (fields (field (name "LCSC PART #") "X"))
      (libsource (lib "JLC_PCB") (part "XT60PW_F"))
    )
    (comp (ref "L0")
      (value "220uH")
      (footprint "SRR1260")
      (description "L - INDUCTOR - 220uH - 1.6A - 12.5mm")
      (fields (field (name "LCSC PART #") "C169380") (field (name "Comment") "SWRB1207S-221MT"))
      (libsource (lib "JLC_PCB") (part "SWRB1207S-221MT"))
    )
    (comp (ref "L1")
      (value "220uH")
      (footprint "SRR1260")
      (description "L - INDUCTOR - 220uH - 1.6A - 12.5mm")
      (fields (field (name "LCSC PART #") "C169380") (field (name "Comment") "SWRB1207S-221MT"))
      (libsource (lib "JLC_PCB") (part "SWRB1207S-221MT"))
    )
    (comp (ref "L2")
      (value "220uH")
      (footprint "SRR1260")
      (description "L - INDUCTOR - 220uH - 1.6A - 12.5mm")
      (fields (field (name "LCSC PART #") "C169380") (field (name "Comment") "SWRB1207S-221MT"))
      (libsource (lib "JLC_PCB") (part "SWRB1207S-221MT"))
    )
    (comp (ref "L3")
      (value "220uH")
      (footprint "SRR1260")
      (description "L - INDUCTOR - 220uH - 1.6A - 12.5mm")
      (fields (field (name "LCSC PART #") "C169380") (field (name "Comment") "SWRB1207S-221MT"))
      (libsource (lib "JLC_PCB") (part "SWRB1207S-221MT"))
    )
    (comp (ref "L4")
      (value "220uH")
      (footprint "SRR1260")
      (description "L - INDUCTOR - 220uH - 1.6A - 12.5mm")
      (fields (field (name "LCSC PART #") "C169380") (field (name "Comment") "SWRB1207S-221MT"))
      (libsource (lib "JLC_PCB") (part "SWRB1207S-221MT"))
    )
    (comp (ref "L5")
      (value "220uH")
      (footprint "SRR1260")
      (description "L - INDUCTOR - 220uH - 1.6A - 12.5mm")
      (fields (field (name "LCSC PART #") "C169380") (field (name "Comment") "SWRB1207S-221MT"))
      (libsource (lib "JLC_PCB") (part "SWRB1207S-221MT"))
    )
    (comp (ref "L6")
      (value "220uH")
      (footprint "SRR1260")
      (description "L - INDUCTOR - 220uH - 1.6A - 12.5mm")
      (fields (field (name "LCSC PART #") "C169380") (field (name "Comment") "SWRB1207S-221MT"))
      (libsource (lib "JLC_PCB") (part "SWRB1207S-221MT"))
    )
    (comp (ref "L7")
      (value "220uH")
      (footprint "SRR1260")
      (description "L - INDUCTOR - 220uH - 1.6A - 12.5mm")
      (fields (field (name "LCSC PART #") "C169380") (field (name "Comment") "SWRB1207S-221MT"))
      (libsource (lib "JLC_PCB") (part "SWRB1207S-221MT"))
    )
    (comp (ref "L8")
      (value "220uH")
      (footprint "SRR1260")
      (description "L - INDUCTOR - 220uH - 1.6A - 12.5mm")
      (fields (field (name "LCSC PART #") "C169380") (field (name "Comment") "SWRB1207S-221MT"))
      (libsource (lib "JLC_PCB") (part "SWRB1207S-221MT"))
    )
    (comp (ref "L9")
      (value "220uH")
      (footprint "SRR1260")
      (description "L - INDUCTOR - 220uH - 1.6A - 12.5mm")
      (fields (field (name "LCSC PART #") "C169380") (field (name "Comment") "SWRB1207S-221MT"))
      (libsource (lib "JLC_PCB") (part "SWRB1207S-221MT"))
    )
    (comp (ref "L10")
      (value "220uH")
      (footprint "SRR1260")
      (description "L - INDUCTOR - 220uH - 1.6A - 12.5mm")
      (fields (field (name "LCSC PART #") "C169380") (field (name "Comment") "SWRB1207S-221MT"))
      (libsource (lib "JLC_PCB") (part "SWRB1207S-221MT"))
    )
    (comp (ref "L11")
      (value "220uH")
      (footprint "SRR1260")
      (description "L - INDUCTOR - 220uH - 1.6A - 12.5mm")
      (fields (field (name "LCSC PART #") "C169380") (field (name "Comment") "SWRB1207S-221MT"))
      (libsource (lib "JLC_PCB") (part "SWRB1207S-221MT"))
    )
    (comp (ref "L12")
      (value "220uH")
      (footprint "SRR1260")
      (description "L - INDUCTOR - 220uH - 1.6A - 12.5mm")
      (fields (field (name "LCSC PART #") "C169380") (field (name "Comment") "SWRB1207S-221MT"))
      (libsource (lib "JLC_PCB") (part "SWRB1207S-221MT"))
    )
    (comp (ref "L13")
      (value "220uH")
      (footprint "SRR1260")
      (description "L - INDUCTOR - 220uH - 1.6A - 12.5mm")
      (fields (field (name "LCSC PART #") "C169380") (field (name "Comment") "SWRB1207S-221MT"))
      (libsource (lib "JLC_PCB") (part "SWRB1207S-221MT"))
    )
    (comp (ref "L14")
      (value "220uH")
      (footprint "SRR1260")
      (description "L - INDUCTOR - 220uH - 1.6A - 12.5mm")
      (fields (field (name "LCSC PART #") "C169380") (field (name "Comment") "SWRB1207S-221MT"))
      (libsource (lib "JLC_PCB") (part "SWRB1207S-221MT"))
    )
    (comp (ref "L15")
      (value "220uH")
      (footprint "SRR1260")
      (description "L - INDUCTOR - 220uH - 1.6A - 12.5mm")
      (fields (field (name "LCSC PART #") "C169380") (field (name "Comment") "SWRB1207S-221MT"))
      (libsource (lib "JLC_PCB") (part "SWRB1207S-221MT"))
    )
    (comp (ref "L16")
      (value "220uH")
      (footprint "SRR1260")
      (description "L - INDUCTOR - 220uH - 1.6A - 12.5mm")
      (fields (field (name "LCSC PART #") "C169380") (field (name "Comment") "SWRB1207S-221MT"))
      (libsource (lib "JLC_PCB") (part "SWRB1207S-221MT"))
    )
    (comp (ref "NT1")
      (value "0")
      (footprint "NET_TIE")
      (description "R - Net Tie")
      (libsource (lib "JLC_PCB") (part "NET_TIE"))
    )
    (comp (ref "NT2")
      (value "0")
      (footprint "NET_TIE")
      (description "R - Net Tie")
      (libsource (lib "JLC_PCB") (part "NET_TIE"))
    )
    (comp (ref "Q1")
      (value "IRF9540NSTRLPBF")
      (footprint "TO-263-3")
      (description "Q - TRANSISTOR - MOSFET (N) - 250V - 33A - 0.094R")
      (fields (field (name "LCSC PART #") "C33903"))
      (libsource (lib "JLC_PCB") (part "IRF9540NSTRLPBF"))
    )
    (comp (ref "Q2")
      (value "IRF9540NSTRLPBF")
      (footprint "TO-263-3")
      (description "Q - TRANSISTOR - MOSFET (N) - 250V - 33A - 0.094R")
      (fields (field (name "LCSC PART #") "C33903"))
      (libsource (lib "JLC_PCB") (part "IRF9540NSTRLPBF"))
    )
    (comp (ref "Q3")
      (value "IRF9540NSTRLPBF")
      (footprint "TO-263-3")
      (description "Q - TRANSISTOR - MOSFET (N) - 250V - 33A - 0.094R")
      (fields (field (name "LCSC PART #") "C33903"))
      (libsource (lib "JLC_PCB") (part "IRF9540NSTRLPBF"))
    )
    (comp (ref "Q4")
      (value "IRF9540NSTRLPBF")
      (footprint "TO-263-3")
      (description "Q - TRANSISTOR - MOSFET (N) - 250V - 33A - 0.094R")
      (fields (field (name "LCSC PART #") "C33903"))
      (libsource (lib "JLC_PCB") (part "IRF9540NSTRLPBF"))
    )
    (comp (ref "Q_I2C1")
      (value "2N7002")
      (footprint "TO-236AB")
      (description "Q - TRANSISTOR - MOSFET (N) - 60V - 200mW")
      (fields (field (name "LCSC PART #") "C8545"))
      (libsource (lib "JLC_PCB") (part "2N7002"))
    )
    (comp (ref "Q_I2C2")
      (value "2N7002")
      (footprint "TO-236AB")
      (description "Q - TRANSISTOR - MOSFET (N) - 60V - 200mW")
      (fields (field (name "LCSC PART #") "C8545"))
      (libsource (lib "JLC_PCB") (part "2N7002"))
    )
    (comp (ref "Q_LEDA")
      (value "2N7002")
      (footprint "TO-236AB")
      (description "Q - TRANSISTOR - MOSFET (N) - 60V - 200mW")
      (fields (field (name "LCSC PART #") "C8545"))
      (libsource (lib "JLC_PCB") (part "2N7002"))
    )
    (comp (ref "Q_LEDB")
      (value "2N7002")
      (footprint "TO-236AB")
      (description "Q - TRANSISTOR - MOSFET (N) - 60V - 200mW")
      (fields (field (name "LCSC PART #") "C8545"))
      (libsource (lib "JLC_PCB") (part "2N7002"))
    )
    (comp (ref "Q_LEDVSS")
      (value "2N7002")
      (footprint "TO-236AB")
      (description "Q - TRANSISTOR - MOSFET (N) - 60V - 200mW")
      (fields (field (name "LCSC PART #") "C8545"))
      (libsource (lib "JLC_PCB") (part "2N7002"))
    )
    (comp (ref "R1")
      (value "1m")
      (footprint "R_2512")
      (description "R - RESISTOR - SMD - 0.001R - 1% - 2512 - 2W - 50ppm/k")
      (fields (field (name "LCSC PART #") "C349153") (field (name "POWER") "2W"))
      (libsource (lib "JLC_PCB") (part "EWSL2512F1L00S9"))
    )
    (comp (ref "R2")
      (value "1m")
      (footprint "R_2512")
      (description "R - RESISTOR - SMD - 0.001R - 1% - 2512 - 2W - 50ppm/k")
      (fields (field (name "LCSC PART #") "C349153") (field (name "POWER") "2W"))
      (libsource (lib "JLC_PCB") (part "EWSL2512F1L00S9"))
    )
    (comp (ref "R3")
      (value "10k")
      (footprint "R_0402")
      (description "R - RESISTOR - SMD - 10k - 1% - 0402")
      (fields (field (name "LCSC PART #") "C25744") (field (name "Comment") "0402WGF1002TCE"))
      (libsource (lib "JLC_PCB") (part "0402WGF1002TCE"))
    )
    (comp (ref "R4")
      (value "10k")
      (footprint "R_0402")
      (description "R - RESISTOR - SMD - 10k - 1% - 0402")
      (fields (field (name "LCSC PART #") "C25744") (field (name "Comment") "0402WGF1002TCE"))
      (libsource (lib "JLC_PCB") (part "0402WGF1002TCE"))
    )
    (comp (ref "R5")
      (value "33k")
      (footprint "R_0402")
      (description "R - RESISTOR - SMD - 33k - 1% - 0402")
      (fields (field (name "LCSC PART #") "C25779") (field (name "Comment") "0402WGF3302TCE"))
      (libsource (lib "JLC_PCB") (part "0402WGF3302TCE"))
    )
    (comp (ref "R5_a")
      (value "100k")
      (footprint "R_0402")
      (description "R - RESISTOR - SMD - 100k - 1% -  0402")
      (fields (field (name "LCSC PART #") "C25741") (field (name "Comment") "0402WGF1003TCE"))
      (libsource (lib "JLC_PCB") (part "0402WGF1003TCE"))
    )
    (comp (ref "R6")
      (value "1m")
      (footprint "R_2512")
      (description "R - RESISTOR - SMD - 0.001R - 1% - 2512 - 2W - 50ppm/k")
      (fields (field (name "LCSC PART #") "C349153") (field (name "POWER") "2W"))
      (libsource (lib "JLC_PCB") (part "EWSL2512F1L00S9"))
    )
    (comp (ref "R8")
      (value "220R")
      (footprint "R_0402")
      (description "R - RESISTOR - SMD - 220R - 1% - 0402")
      (fields (field (name "LCSC PART #") "C25091") (field (name "Comment") "0402WGF2200TCE"))
      (libsource (lib "JLC_PCB") (part "0402WGF2200TCE"))
    )
    (comp (ref "R8_A")
      (value "220R")
      (footprint "R_0402")
      (description "R - RESISTOR - SMD - 220R - 1% - 0402")
      (fields (field (name "LCSC PART #") "C25091"))
      (libsource (lib "*") (part "0402WGF2200TCE"))
    )
    (comp (ref "R9")
      (value "10k")
      (footprint "R_0402")
      (description "R - RESISTOR - SMD - 10k - 1% - 0402")
      (fields (field (name "LCSC PART #") "C25744") (field (name "Comment") "0402WGF1002TCE"))
      (libsource (lib "JLC_PCB") (part "0402WGF1002TCE"))
    )
    (comp (ref "R10")
      (value "1m")
      (footprint "R_2512")
      (description "R - RESISTOR - SMD - 0.001R - 1% - 2512 - 2W - 50ppm/k")
      (fields (field (name "LCSC PART #") "C349153") (field (name "POWER") "2W"))
      (libsource (lib "JLC_PCB") (part "EWSL2512F1L00S9"))
    )
    (comp (ref "R11")
      (value "10R")
      (footprint "R_1206")
      (description "R - RESISTOR - SMD - 10R - 1% - 1206")
      (fields (field (name "LCSC PART #") "C17903") (field (name "Comment") "1206W4F100JT5E"))
      (libsource (lib "JLC_PCB") (part "1206W4F100JT5E"))
    )
    (comp (ref "R12")
      (value "220R")
      (footprint "R_0402")
      (description "R - RESISTOR - SMD - 220R - 1% - 0402")
      (fields (field (name "LCSC PART #") "C25091") (field (name "Comment") "0402WGF2200TCE"))
      (libsource (lib "JLC_PCB") (part "0402WGF2200TCE"))
    )
    (comp (ref "R12_A")
      (value "220R")
      (footprint "R_0402")
      (description "R - RESISTOR - SMD - 220R - 1% - 0402")
      (fields (field (name "LCSC PART #") "C25091") (field (name "Comment") "0402WGF2200TCE"))
      (libsource (lib "JLC_PCB") (part "0402WGF2200TCE"))
    )
    (comp (ref "R13")
      (value "100k")
      (footprint "R_0603")
      (description "R - RESISTOR - SMD - 100k - 1% -  0603")
      (fields (field (name "LCSC PART #") "C22936") (field (name "Comment") "0603WAF100KT5E"))
      (libsource (lib "JLC_PCB") (part "0603WAF100KT5E"))
    )
    (comp (ref "R14")
      (value "10R")
      (footprint "R_1206")
      (description "R - RESISTOR - SMD - 10R - 1% - 1206")
      (fields (field (name "LCSC PART #") "C17903") (field (name "Comment") "1206W4F100JT5E"))
      (libsource (lib "JLC_PCB") (part "1206W4F100JT5E"))
    )
    (comp (ref "R15")
      (value "3.3k")
      (footprint "R_0402")
      (description "R - RESISTOR - SMD - 3.3k - 1% - 0402")
      (fields (field (name "LCSC PART #") "C25890") (field (name "Comment") "0402WGF3301TCE"))
      (libsource (lib "JLC_PCB") (part "0402WGF3301TCE"))
    )
    (comp (ref "R16")
      (value "0R")
      (footprint "R_0402")
      (description "R - RESISTOR - SMD - 0R - 1% - 0402")
      (fields (field (name "LCSC PART #") "C17168") (field (name "Comment") "0402WGF0000TCE"))
      (libsource (lib "JLC_PCB") (part "0402WGF0000TCE"))
    )
    (comp (ref "R17")
      (value "0R")
      (footprint "R_0402")
      (description "R - RESISTOR - SMD - 0R - 1% - 0402")
      (fields (field (name "LCSC PART #") "C17168") (field (name "Comment") "0402WGF0000TCE"))
      (libsource (lib "JLC_PCB") (part "0402WGF0000TCE"))
    )
    (comp (ref "R18")
      (value "10R")
      (footprint "R_0402")
      (description "R - RESISTOR - SMD - 10R - 1% - 0402")
      (fields (field (name "LCSC PART #") "C25077") (field (name "Comment") "0402WGF100JTCE"))
      (libsource (lib "JLC_PCB") (part "0402WGF100JTCE"))
    )
    (comp (ref "R18_a")
      (value "10R")
      (footprint "R_0402")
      (description "R - RESISTOR - SMD - 10R - 1% - 0402")
      (fields (field (name "LCSC PART #") "C25077") (field (name "Comment") "0402WGF100JTCE"))
      (libsource (lib "JLC_PCB") (part "0402WGF100JTCE"))
    )
    (comp (ref "R19")
      (value "10R")
      (footprint "R_0402")
      (description "R - RESISTOR - SMD - 10R - 1% - 0402")
      (fields (field (name "LCSC PART #") "C25077") (field (name "Comment") "0402WGF100JTCE"))
      (libsource (lib "JLC_PCB") (part "0402WGF100JTCE"))
    )
    (comp (ref "R19_a")
      (value "10R")
      (footprint "R_0402")
      (description "R - RESISTOR - SMD - 10R - 1% - 0402")
      (fields (field (name "LCSC PART #") "C25077") (field (name "Comment") "0402WGF100JTCE"))
      (libsource (lib "JLC_PCB") (part "0402WGF100JTCE"))
    )
    (comp (ref "R20")
      (value "4.7k")
      (footprint "R_0402")
      (description "R - RESISTOR - SMD - 4.7k - 1% - 0402")
      (fields (field (name "LCSC PART #") "C25900") (field (name "Comment") "0402WGF4701TCE"))
      (libsource (lib "JLC_PCB") (part "0402WGF4701TCE"))
    )
    (comp (ref "R21")
      (value "10R")
      (footprint "R_0402")
      (description "R - RESISTOR - SMD - 10R - 1% - 0402")
      (fields (field (name "LCSC PART #") "C25077") (field (name "Comment") "0402WGF100JTCE"))
      (libsource (lib "JLC_PCB") (part "0402WGF100JTCE"))
    )
    (comp (ref "R22")
      (value "10k")
      (footprint "R_0402")
      (description "R - RESISTOR - SMD - 10k - 1% - 0402")
      (fields (field (name "LCSC PART #") "C25744") (field (name "Comment") "0402WGF1002TCE"))
      (libsource (lib "JLC_PCB") (part "0402WGF1002TCE"))
    )
    (comp (ref "R23")
      (value "10k")
      (footprint "R_0402")
      (description "R - RESISTOR - SMD - 10k - 1% - 0402")
      (fields (field (name "LCSC PART #") "C25744") (field (name "Comment") "0402WGF1002TCE"))
      (libsource (lib "JLC_PCB") (part "0402WGF1002TCE"))
    )
    (comp (ref "R24")
      (value "220R")
      (footprint "R_0402")
      (description "R - RESISTOR - SMD - 220R - 1% - 0402")
      (fields (field (name "LCSC PART #") "C25091") (field (name "Comment") "0402WGF2200TCE"))
      (libsource (lib "JLC_PCB") (part "0402WGF2200TCE"))
    )
    (comp (ref "R24_A")
      (value "220R")
      (footprint "R_0402")
      (description "R - RESISTOR - SMD - 220R - 1% - 0402")
      (fields (field (name "LCSC PART #") "C25091") (field (name "Comment") "0402WGF2200TCE"))
      (libsource (lib "JLC_PCB") (part "0402WGF2200TCE"))
    )
    (comp (ref "R24_B")
      (value "220R")
      (footprint "R_0402")
      (description "R - RESISTOR - SMD - 220R - 1% - 0402")
      (fields (field (name "LCSC PART #") "C25091") (field (name "Comment") "0402WGF2200TCE"))
      (libsource (lib "JLC_PCB") (part "0402WGF2200TCE"))
    )
    (comp (ref "R25")
      (value "0R")
      (footprint "R_0402")
      (description "R - RESISTOR - SMD - 0R - 1% - 0402")
      (fields (field (name "LCSC PART #") "C17168") (field (name "Comment") "0402WGF0000TCE"))
      (libsource (lib "JLC_PCB") (part "0402WGF0000TCE"))
    )
    (comp (ref "R26")
      (value "10k")
      (footprint "R_0402")
      (description "R - RESISTOR - SMD - 10k - 1% - 0402")
      (fields (field (name "LCSC PART #") "C25744") (field (name "Comment") "0402WGF1002TCE"))
      (libsource (lib "JLC_PCB") (part "0402WGF1002TCE"))
    )
    (comp (ref "R28")
      (value "33k")
      (footprint "R_0402")
      (description "R - RESISTOR - SMD - 33k - 1% - 0402")
      (fields (field (name "LCSC PART #") "C25779") (field (name "Comment") "0402WGF3302TCE"))
      (libsource (lib "JLC_PCB") (part "0402WGF3302TCE"))
    )
    (comp (ref "R29")
      (value "0R")
      (footprint "R_0402")
      (description "R - RESISTOR - SMD - 0R - 1% - 0402")
      (fields (field (name "LCSC PART #") "C17168") (field (name "Comment") "0402WGF0000TCE"))
      (libsource (lib "JLC_PCB") (part "0402WGF0000TCE"))
    )
    (comp (ref "R30")
      (value "0R")
      (footprint "R_0402")
      (description "R - RESISTOR - SMD - 0R - 1% - 0402")
      (fields (field (name "LCSC PART #") "C17168") (field (name "Comment") "0402WGF0000TCE"))
      (libsource (lib "JLC_PCB") (part "0402WGF0000TCE"))
    )
    (comp (ref "R31")
      (value "0R")
      (footprint "R_0402")
      (description "R - RESISTOR - SMD - 0R - 1% - 0402")
      (fields (field (name "LCSC PART #") "C17168") (field (name "Comment") "0402WGF0000TCE"))
      (libsource (lib "JLC_PCB") (part "0402WGF0000TCE"))
    )
    (comp (ref "R32")
      (value "10R")
      (footprint "R_0402")
      (description "R - RESISTOR - SMD - 10R - 1% - 0402")
      (fields (field (name "LCSC PART #") "C25077") (field (name "Comment") "0402WGF100JTCE"))
      (libsource (lib "JLC_PCB") (part "0402WGF100JTCE"))
    )
    (comp (ref "R32_a")
      (value "10R")
      (footprint "R_0402")
      (description "R - RESISTOR - SMD - 10R - 1% - 0402")
      (fields (field (name "LCSC PART #") "C25077") (field (name "Comment") "0402WGF100JTCE"))
      (libsource (lib "JLC_PCB") (part "0402WGF100JTCE"))
    )
    (comp (ref "R33")
      (value "10R")
      (footprint "R_0402")
      (description "R - RESISTOR - SMD - 10R - 1% - 0402")
      (fields (field (name "LCSC PART #") "C25077") (field (name "Comment") "0402WGF100JTCE"))
      (libsource (lib "JLC_PCB") (part "0402WGF100JTCE"))
    )
    (comp (ref "R33_a")
      (value "10R")
      (footprint "R_0402")
      (description "R - RESISTOR - SMD - 10R - 1% - 0402")
      (fields (field (name "LCSC PART #") "C25077") (field (name "Comment") "0402WGF100JTCE"))
      (libsource (lib "JLC_PCB") (part "0402WGF100JTCE"))
    )
    (comp (ref "R34")
      (value "220R")
      (footprint "R_0402")
      (description "R - RESISTOR - SMD - 220R - 1% - 0402")
      (fields (field (name "LCSC PART #") "C25091") (field (name "Comment") "0402WGF2200TCE"))
      (libsource (lib "JLC_PCB") (part "0402WGF2200TCE"))
    )
    (comp (ref "R35")
      (value "0R")
      (footprint "R_0402")
      (description "R - RESISTOR - SMD - 0R - 1% - 0402")
      (fields (field (name "LCSC PART #") "C17168") (field (name "Comment") "0402WGF0000TCE"))
      (libsource (lib "JLC_PCB") (part "0402WGF0000TCE"))
    )
    (comp (ref "R36")
      (value "10k")
      (footprint "R_0402")
      (description "R - RESISTOR - SMD - 10k - 1% - 0402")
      (fields (field (name "LCSC PART #") "C25744") (field (name "Comment") "0402WGF1002TCE"))
      (libsource (lib "JLC_PCB") (part "0402WGF1002TCE"))
    )
    (comp (ref "R37")
      (value "0R")
      (footprint "R_0402")
      (description "R - RESISTOR - SMD - 0R - 1% - 0402")
      (fields (field (name "LCSC PART #") "C17168") (field (name "Comment") "0402WGF0000TCE"))
      (libsource (lib "JLC_PCB") (part "0402WGF0000TCE"))
    )
    (comp (ref "R38")
      (value "4.7k")
      (footprint "R_0402")
      (description "R - RESISTOR - SMD - 4.7k - 1% - 0402")
      (fields (field (name "LCSC PART #") "C25900") (field (name "Comment") "0402WGF4701TCE"))
      (libsource (lib "JLC_PCB") (part "0402WGF4701TCE"))
    )
    (comp (ref "R39")
      (value "1M")
      (footprint "R_0402")
      (description "R - RESISTOR - SMD - 1M - 1% - 0402")
      (fields (field (name "LCSC PART #") "C26083") (field (name "Comment") "0402WGF1004TCE"))
      (libsource (lib "JLC_PCB") (part "0402WGF1004TCE"))
    )
    (comp (ref "R40")
      (value "1M")
      (footprint "R_0402")
      (description "R - RESISTOR - SMD - 1M - 1% - 0402")
      (fields (field (name "LCSC PART #") "C26083") (field (name "Comment") "0402WGF1004TCE"))
      (libsource (lib "JLC_PCB") (part "0402WGF1004TCE"))
    )
    (comp (ref "R41")
      (value "100k")
      (footprint "R_0402")
      (description "R - RESISTOR - SMD - 100k - 1% -  0402")
      (fields (field (name "LCSC PART #") "C25741") (field (name "Comment") "0402WGF1003TCE"))
      (libsource (lib "JLC_PCB") (part "0402WGF1003TCE"))
    )
    (comp (ref "R42")
      (value "10k")
      (footprint "R_0402")
      (description "R - RESISTOR - SMD - 10k - 1% - 0402")
      (fields (field (name "LCSC PART #") "C25744") (field (name "Comment") "0402WGF1002TCE"))
      (libsource (lib "JLC_PCB") (part "0402WGF1002TCE"))
    )
    (comp (ref "R43")
      (value "10k")
      (footprint "R_0402")
      (description "R - RESISTOR - SMD - 10k - 1% - 0402")
      (fields (field (name "LCSC PART #") "C25744") (field (name "Comment") "0402WGF1002TCE"))
      (libsource (lib "JLC_PCB") (part "0402WGF1002TCE"))
    )
    (comp (ref "R44")
      (value "0R")
      (footprint "R_0402")
      (description "R - RESISTOR - SMD - 0R - 1% - 0402")
      (fields (field (name "LCSC PART #") "C17168") (field (name "Comment") "0402WGF0000TCE"))
      (libsource (lib "JLC_PCB") (part "0402WGF0000TCE"))
    )
    (comp (ref "R45")
      (value "10k")
      (footprint "R_0402")
      (description "R - RESISTOR - SMD - 10k - 1% - 0402")
      (fields (field (name "LCSC PART #") "C25744") (field (name "Comment") "0402WGF1002TCE"))
      (libsource (lib "JLC_PCB") (part "0402WGF1002TCE"))
    )
    (comp (ref "R47")
      (value "10k")
      (footprint "R_0402")
      (description "R - RESISTOR - SMD - 10k - 1% - 0402")
      (fields (field (name "LCSC PART #") "C25744") (field (name "Comment") "0402WGF1002TCE"))
      (libsource (lib "JLC_PCB") (part "0402WGF1002TCE"))
    )
    (comp (ref "R48")
      (value "10k")
      (footprint "R_0402")
      (description "R - RESISTOR - SMD - 10k - 1% - 0402")
      (fields (field (name "LCSC PART #") "C25744") (field (name "Comment") "0402WGF1002TCE"))
      (libsource (lib "JLC_PCB") (part "0402WGF1002TCE"))
    )
    (comp (ref "R51")
      (value "100k")
      (footprint "R_0603")
      (description "R - RESISTOR - SMD - 100k - 1% -  0603")
      (fields (field (name "LCSC PART #") "C22936") (field (name "Comment") "0603WAF100KT5E"))
      (libsource (lib "JLC_PCB") (part "0603WAF100KT5E"))
    )
    (comp (ref "R53")
      (value "4.7k")
      (footprint "R_0402")
      (description "R - RESISTOR - SMD - 4.7k - 1% - 0402")
      (fields (field (name "LCSC PART #") "C25900") (field (name "Comment") "0402WGF4701TCE"))
      (libsource (lib "JLC_PCB") (part "0402WGF4701TCE"))
    )
    (comp (ref "R56")
      (value "47k")
      (footprint "R_0402")
      (description "R - RESISTOR - SMD - 47k - 1% - 0402")
      (fields (field (name "LCSC PART #") "C25792") (field (name "Comment") "0402WGF4702TCE"))
      (libsource (lib "JLC_PCB") (part "0402WGF4702TCE"))
    )
    (comp (ref "R87_a")
      (value "47k")
      (footprint "R_0402")
      (description "R - RESISTOR - SMD - 47k - 1% - 0402")
      (fields (field (name "LCSC PART #") "C25792") (field (name "Comment") "0402WGF4702TCE"))
      (libsource (lib "JLC_PCB") (part "0402WGF4702TCE"))
    )
    (comp (ref "R100")
      (value "1k")
      (footprint "R_0402")
      (description "R - RESISTOR - SMD - 1k - 1% - 0402")
      (fields (field (name "LCSC PART #") "C11702") (field (name "Comment") "0402WGF1001TCE"))
      (libsource (lib "JLC_PCB") (part "0402WGF1001TCE"))
    )
    (comp (ref "R101")
      (value "1k")
      (footprint "R_0402")
      (description "R - RESISTOR - SMD - 1k - 1% - 0402")
      (fields (field (name "LCSC PART #") "C11702") (field (name "Comment") "0402WGF1001TCE"))
      (libsource (lib "JLC_PCB") (part "0402WGF1001TCE"))
    )
    (comp (ref "R102")
      (value "1k")
      (footprint "R_0402")
      (description "R - RESISTOR - SMD - 1k - 1% - 0402")
      (fields (field (name "LCSC PART #") "C11702") (field (name "Comment") "0402WGF1001TCE"))
      (libsource (lib "JLC_PCB") (part "0402WGF1001TCE"))
    )
    (comp (ref "R103")
      (value "1k")
      (footprint "R_0402")
      (description "R - RESISTOR - SMD - 1k - 1% - 0402")
      (fields (field (name "LCSC PART #") "C11702") (field (name "Comment") "0402WGF1001TCE"))
      (libsource (lib "JLC_PCB") (part "0402WGF1001TCE"))
    )
    (comp (ref "R116")
      (value "47k")
      (footprint "R_0402")
      (description "R - RESISTOR - SMD - 47k - 1% - 0402")
      (fields (field (name "LCSC PART #") "C25792") (field (name "Comment") "0402WGF4702TCE"))
      (libsource (lib "JLC_PCB") (part "0402WGF4702TCE"))
    )
    (comp (ref "R121")
      (value "10k")
      (footprint "R_0402")
      (description "R - RESISTOR - SMD - 10k - 1% - 0402")
      (fields (field (name "LCSC PART #") "C25744") (field (name "Comment") "0402WGF1002TCE"))
      (libsource (lib "JLC_PCB") (part "0402WGF1002TCE"))
    )
    (comp (ref "RA1_N")
      (value "0R")
      (footprint "R_0402")
      (description "R - RESISTOR - SMD - 0R - 1% - 0402")
      (fields (field (name "LCSC PART #") "C17168") (field (name "Comment") "0402WGF0000TCE"))
      (libsource (lib "JLC_PCB") (part "0402WGF0000TCE"))
    )
    (comp (ref "RA1_P")
      (value "0R")
      (footprint "R_0402")
      (description "R - RESISTOR - SMD - 0R - 1% - 0402")
      (fields (field (name "LCSC PART #") "C17168") (field (name "Comment") "0402WGF0000TCE"))
      (libsource (lib "JLC_PCB") (part "0402WGF0000TCE"))
    )
    (comp (ref "RA2_N")
      (value "0R")
      (footprint "R_0402")
      (description "R - RESISTOR - SMD - 0R - 1% - 0402")
      (fields (field (name "LCSC PART #") "C17168") (field (name "Comment") "0402WGF0000TCE"))
      (libsource (lib "JLC_PCB") (part "0402WGF0000TCE"))
    )
    (comp (ref "RA2_P")
      (value "0R")
      (footprint "R_0402")
      (description "R - RESISTOR - SMD - 0R - 1% - 0402")
      (fields (field (name "LCSC PART #") "C17168") (field (name "Comment") "0402WGF0000TCE"))
      (libsource (lib "JLC_PCB") (part "0402WGF0000TCE"))
    )
    (comp (ref "RB1_N")
      (value "0R")
      (footprint "R_0402")
      (description "R - RESISTOR - SMD - 0R - 1% - 0402")
      (fields (field (name "LCSC PART #") "C17168") (field (name "Comment") "0402WGF0000TCE"))
      (libsource (lib "JLC_PCB") (part "0402WGF0000TCE"))
    )
    (comp (ref "RB1_P")
      (value "0R")
      (footprint "R_0402")
      (description "R - RESISTOR - SMD - 0R - 1% - 0402")
      (fields (field (name "LCSC PART #") "C17168") (field (name "Comment") "0402WGF0000TCE"))
      (libsource (lib "JLC_PCB") (part "0402WGF0000TCE"))
    )
    (comp (ref "RB2_N")
      (value "0R")
      (footprint "R_0402")
      (description "R - RESISTOR - SMD - 0R - 1% - 0402")
      (fields (field (name "LCSC PART #") "C17168") (field (name "Comment") "0402WGF0000TCE"))
      (libsource (lib "JLC_PCB") (part "0402WGF0000TCE"))
    )
    (comp (ref "RB2_P")
      (value "0R")
      (footprint "R_0402")
      (description "R - RESISTOR - SMD - 0R - 1% - 0402")
      (fields (field (name "LCSC PART #") "C17168") (field (name "Comment") "0402WGF0000TCE"))
      (libsource (lib "JLC_PCB") (part "0402WGF0000TCE"))
    )
    (comp (ref "Ron_a")
      (value "100k")
      (footprint "R_0402")
      (description "R - RESISTOR - SMD - 100k - 1% -  0402")
      (fields (field (name "LCSC PART #") "C25741") (field (name "Comment") "0402WGF1003TCE"))
      (libsource (lib "JLC_PCB") (part "0402WGF1003TCE"))
    )
    (comp (ref "Ron_b")
      (value "100k")
      (footprint "R_0402")
      (description "R - RESISTOR - SMD - 100k - 1% -  0402")
      (fields (field (name "LCSC PART #") "C25741") (field (name "Comment") "0402WGF1003TCE"))
      (libsource (lib "JLC_PCB") (part "0402WGF1003TCE"))
    )
    (comp (ref "Ron_c")
      (value "100k")
      (footprint "R_0402")
      (description "R - RESISTOR - SMD - 100k - 1% -  0402")
      (fields (field (name "LCSC PART #") "C25741") (field (name "Comment") "0402WGF1003TCE"))
      (libsource (lib "JLC_PCB") (part "0402WGF1003TCE"))
    )
    (comp (ref "Ron_d")
      (value "100k")
      (footprint "R_0402")
      (description "R - RESISTOR - SMD - 100k - 1% -  0402")
      (fields (field (name "LCSC PART #") "C25741") (field (name "Comment") "0402WGF1003TCE"))
      (libsource (lib "JLC_PCB") (part "0402WGF1003TCE"))
    )
    (comp (ref "R_1A_a")
      (value "47k")
      (footprint "R_0402")
      (description "R - RESISTOR - SMD - 47k - 1% - 0402")
      (fields (field (name "LCSC PART #") "C25792") (field (name "Comment") "0402WGF4702TCE"))
      (libsource (lib "JLC_PCB") (part "0402WGF4702TCE"))
    )
    (comp (ref "R_1A_b")
      (value "47k")
      (footprint "R_0402")
      (description "R - RESISTOR - SMD - 47k - 1% - 0402")
      (fields (field (name "LCSC PART #") "C25792") (field (name "Comment") "0402WGF4702TCE"))
      (libsource (lib "JLC_PCB") (part "0402WGF4702TCE"))
    )
    (comp (ref "R_1A_c")
      (value "100k")
      (footprint "R_0402")
      (description "R - RESISTOR - SMD - 100k - 1% -  0402")
      (fields (field (name "LCSC PART #") "C25741") (field (name "Comment") "0402WGF1003TCE"))
      (libsource (lib "JLC_PCB") (part "0402WGF1003TCE"))
    )
    (comp (ref "R_1B_a")
      (value "47k")
      (footprint "R_0402")
      (description "R - RESISTOR - SMD - 47k - 1% - 0402")
      (fields (field (name "LCSC PART #") "C25792") (field (name "Comment") "0402WGF4702TCE"))
      (libsource (lib "JLC_PCB") (part "0402WGF4702TCE"))
    )
    (comp (ref "R_1B_b")
      (value "47k")
      (footprint "R_0402")
      (description "R - RESISTOR - SMD - 47k - 1% - 0402")
      (fields (field (name "LCSC PART #") "C25792") (field (name "Comment") "0402WGF4702TCE"))
      (libsource (lib "JLC_PCB") (part "0402WGF4702TCE"))
    )
    (comp (ref "R_1B_c")
      (value "100k")
      (footprint "R_0402")
      (description "R - RESISTOR - SMD - 100k - 1% -  0402")
      (fields (field (name "LCSC PART #") "C25741") (field (name "Comment") "0402WGF1003TCE"))
      (libsource (lib "JLC_PCB") (part "0402WGF1003TCE"))
    )
    (comp (ref "R_LEDA_O")
      (value "0R")
      (footprint "R_0402")
      (description "R - RESISTOR - SMD - 0R - 1% - 0402")
      (fields (field (name "LCSC PART #") "C17168") (field (name "Comment") "0402WGF0000TCE"))
      (libsource (lib "JLC_PCB") (part "0402WGF0000TCE"))
    )
    (comp (ref "R_LEDB_O")
      (value "0R")
      (footprint "R_0402")
      (description "R - RESISTOR - SMD - 0R - 1% - 0402")
      (fields (field (name "LCSC PART #") "C17168") (field (name "Comment") "0402WGF0000TCE"))
      (libsource (lib "JLC_PCB") (part "0402WGF0000TCE"))
    )
    (comp (ref "R_SCL3")
      (value "10k")
      (footprint "R_0402")
      (description "R - RESISTOR - SMD - 10k - 1% - 0402")
      (fields (field (name "LCSC PART #") "C25744") (field (name "Comment") "0402WGF1002TCE"))
      (libsource (lib "JLC_PCB") (part "0402WGF1002TCE"))
    )
    (comp (ref "R_SDA3")
      (value "10k")
      (footprint "R_0402")
      (description "R - RESISTOR - SMD - 10k - 1% - 0402")
      (fields (field (name "LCSC PART #") "C25744") (field (name "Comment") "0402WGF1002TCE"))
      (libsource (lib "JLC_PCB") (part "0402WGF1002TCE"))
    )
    (comp (ref "U1")
      (value "LM5008MMX/NOPB")
      (footprint "SOP65P490X110-8N")
      (description "U - IC - BUCK CONVERTER, ADJUSTABLE, 95V, 350mA")
      (libsource (lib "JLC_PCB") (part "LM5008MMX/NOPB"))
    )
    (comp (ref "U5V")
      (value "L78M05ABDT-TR")
      (footprint "TO-252AA")
      (description "U - IC - 5V Power Regulator")
      (fields (field (name "LCSC PART #") "C58069"))
      (libsource (lib "JLC_PCB") (part "L78M05ABDT-TR"))
    )
    (comp (ref "U7")
      (value "SM72295MAX")
      (footprint "M28B_M")
      (description "Photovoltaic Full Bridge Driver")
      (fields (field (name "MANUFACTURER") "National Semiconductor") (field (name "PARTNUMBER") "SM72295"))
      (libsource (lib "SM_ICs") (part "SM72295"))
    )
    (comp (ref "U8")
      (value "SM72442MTE/NOPB")
      (footprint "MTC28_L")
      (description "Programmable Maximum Power Point Tracking Controller for Photovoltaic Solar Panels")
      (fields (field (name "MANUFACTURER") "National Semiconductor") (field (name "PARTNUMBER") "SM72442"))
      (libsource (lib "SM_ICs") (part "SM72442"))
    )
  )
  (nets
    (net (code "1") (name "+5VDC") (class "Default")
      (node (ref "C32") (pin "2") (pinfunction "2_2") (pintype "passive"))
      (node (ref "C34") (pin "2") (pinfunction "2_2") (pintype "passive"))
      (node (ref "C37") (pin "1") (pinfunction "1_1") (pintype "passive"))
      (node (ref "C38") (pin "2") (pinfunction "2_2") (pintype "passive"))
      (node (ref "C42") (pin "2") (pinfunction "2_2") (pintype "passive"))
      (node (ref "R100") (pin "1") (pinfunction "1_1") (pintype "passive"))
      (node (ref "R101") (pin "1") (pinfunction "1_1") (pintype "passive"))
      (node (ref "R102") (pin "1") (pinfunction "1_1") (pintype "passive"))
      (node (ref "R103") (pin "1") (pinfunction "1_1") (pintype "passive"))
      (node (ref "R17") (pin "2") (pinfunction "2_2") (pintype "passive"))
      (node (ref "R21") (pin "2") (pinfunction "2_2") (pintype "passive"))
      (node (ref "R26") (pin "2") (pinfunction "2_2") (pintype "passive"))
      (node (ref "R28") (pin "2") (pinfunction "2_2") (pintype "passive"))
      (node (ref "R29") (pin "2") (pinfunction "2_2") (pintype "passive"))
      (node (ref "R30") (pin "1") (pinfunction "1_1") (pintype "passive"))
      (node (ref "R31") (pin "2") (pinfunction "2_2") (pintype "passive"))
      (node (ref "R36") (pin "1") (pinfunction "1_1") (pintype "passive"))
      (node (ref "R45") (pin "1") (pinfunction "1_1") (pintype "passive"))
      (node (ref "R47") (pin "2") (pinfunction "2_2") (pintype "passive"))
      (node (ref "R48") (pin "2") (pinfunction "2_2") (pintype "passive"))
      (node (ref "R87_a") (pin "2") (pinfunction "2_2") (pintype "passive"))
      (node (ref "U7") (pin "17") (pinfunction "VDD_17") (pintype "power_in"))
      (node (ref "U8") (pin "3") (pinfunction "VDDD_3") (pintype "power_in"))
    )
    (net (code "2") (name "/1A_GATE") (class "Default")
      (node (ref "D_1A") (pin "2") (pinfunction "A_2") (pintype "passive"))
      (node (ref "D_1A_G") (pin "1") (pinfunction "K_1") (pintype "passive"))
      (node (ref "Q_LEDA") (pin "1") (pinfunction "G_1") (pintype "passive"))
      (node (ref "R_1A_b") (pin "2") (pinfunction "2_2") (pintype "passive"))
      (node (ref "R_1A_c") (pin "2") (pinfunction "2_2") (pintype "passive"))
    )
    (net (code "3") (name "/1B_GATE") (class "Default")
      (node (ref "D_1B") (pin "2") (pinfunction "A_2") (pintype "passive"))
      (node (ref "D_1B_G") (pin "1") (pinfunction "K_1") (pintype "passive"))
      (node (ref "R_1B_b") (pin "2") (pinfunction "2_2") (pintype "passive"))
      (node (ref "R_1B_c") (pin "2") (pinfunction "2_2") (pintype "passive"))
    )
    (net (code "4") (name "/3V3_SCL") (class "Default")
      (node (ref "Q_I2C1") (pin "2") (pinfunction "S_2") (pintype "passive"))
      (node (ref "R_SCL3") (pin "1") (pinfunction "1_1") (pintype "passive"))
    )
    (net (code "5") (name "/3V3_SDA") (class "Default")
      (node (ref "Q_I2C2") (pin "2") (pinfunction "S_2") (pintype "passive"))
      (node (ref "R_SDA3") (pin "1") (pinfunction "1_1") (pintype "passive"))
    )
    (net (code "6") (name "/5V_SCL") (class "Default")
      (node (ref "Q_I2C1") (pin "3") (pinfunction "D_3") (pintype "passive"))
      (node (ref "R48") (pin "1") (pinfunction "1_1") (pintype "passive"))
      (node (ref "U8") (pin "8") (pinfunction "SCL_8") (pintype "input"))
    )
    (net (code "7") (name "/5V_SDA") (class "Default")
      (node (ref "Q_I2C2") (pin "3") (pinfunction "D_3") (pintype "passive"))
      (node (ref "R47") (pin "1") (pinfunction "1_1") (pintype "passive"))
      (node (ref "U8") (pin "9") (pinfunction "SDA_9") (pintype "bidirectional"))
    )
    (net (code "8") (name "/A1_N") (class "Default")
      (node (ref "R12") (pin "1") (pinfunction "1_1") (pintype "passive"))
      (node (ref "RA1_P") (pin "2") (pinfunction "2_2") (pintype "passive"))
      (node (ref "RA2_P") (pin "2") (pinfunction "2_2") (pintype "passive"))
    )
    (net (code "9") (name "/A1_P") (class "Default")
      (node (ref "R8") (pin "1") (pinfunction "1_1") (pintype "passive"))
      (node (ref "RA1_N") (pin "2") (pinfunction "2_2") (pintype "passive"))
      (node (ref "RA2_N") (pin "2") (pinfunction "2_2") (pintype "passive"))
    )
    (net (code "10") (name "/A2_N") (class "Default")
      (node (ref "R24_A") (pin "2") (pinfunction "2_2") (pintype "passive"))
      (node (ref "RB1_N") (pin "2") (pinfunction "2_2") (pintype "passive"))
      (node (ref "RB2_N") (pin "2") (pinfunction "2_2") (pintype "passive"))
    )
    (net (code "11") (name "/A2_P") (class "Default")
      (node (ref "R24_B") (pin "2") (pinfunction "2_2") (pintype "passive"))
      (node (ref "RB1_P") (pin "2") (pinfunction "2_2") (pintype "passive"))
      (node (ref "RB2_P") (pin "2") (pinfunction "2_2") (pintype "passive"))
    )
    (net (code "12") (name "/AIIN") (class "Default")
      (node (ref "C58") (pin "2") (pinfunction "2_2") (pintype "passive"))
      (node (ref "R44") (pin "1") (pinfunction "1_1") (pintype "passive"))
      (node (ref "U8") (pin "19") (pinfunction "AIIN_19") (pintype "input"))
    )
    (net (code "13") (name "/AIOUT") (class "Default")
      (node (ref "C60") (pin "2") (pinfunction "2_2") (pintype "passive"))
      (node (ref "R37") (pin "1") (pinfunction "1_1") (pintype "passive"))
      (node (ref "U8") (pin "21") (pinfunction "AIOUT_21") (pintype "output"))
    )
    (net (code "14") (name "/AVIN") (class "Default")
      (node (ref "C29") (pin "2") (pinfunction "2_2") (pintype "passive"))
      (node (ref "R13") (pin "1") (pinfunction "1_1") (pintype "passive"))
      (node (ref "R20") (pin "1") (pinfunction "1_1") (pintype "passive"))
      (node (ref "U8") (pin "15") (pinfunction "AVIN_15") (pintype "input"))
    )
    (net (code "15") (name "/AVOUT") (class "Default")
      (node (ref "C59") (pin "2") (pinfunction "2_2") (pintype "passive"))
      (node (ref "R51") (pin "1") (pinfunction "1_1") (pintype "passive"))
      (node (ref "R53") (pin "1") (pinfunction "1_1") (pintype "passive"))
      (node (ref "U8") (pin "17") (pinfunction "AVOUT_17") (pintype "output"))
    )
    (net (code "16") (name "/BIN") (class "Default")
      (node (ref "R37") (pin "2") (pinfunction "2_2") (pintype "passive"))
      (node (ref "U7") (pin "4") (pinfunction "BIN_4") (pintype "output"))
    )
    (net (code "17") (name "/BOUT") (class "Default")
      (node (ref "R44") (pin "2") (pinfunction "2_2") (pintype "passive"))
      (node (ref "U7") (pin "11") (pinfunction "BOUT_11") (pintype "output"))
    )
    (net (code "18") (name "/GND_OUT") (class "Default")
      (node (ref "J_OUT") (pin "MINUS") (pinfunction "-_MINUS") (pintype "passive"))
      (node (ref "R6") (pin "2") (pinfunction "2_2") (pintype "passive"))
      (node (ref "RA2_P") (pin "1") (pinfunction "1_1") (pintype "passive"))
    )
    (net (code "19") (name "/HIA") (class "Default")
      (node (ref "U7") (pin "7") (pinfunction "HIA_7") (pintype "input"))
      (node (ref "U8") (pin "26") (pinfunction "HIA_26") (pintype "output"))
    )
    (net (code "20") (name "/HIB") (class "Default")
      (node (ref "U7") (pin "8") (pinfunction "HIB_8") (pintype "input"))
      (node (ref "U8") (pin "25") (pinfunction "HIB_25") (pintype "output"))
    )
    (net (code "21") (name "/HO_A") (class "Default")
      (node (ref "D3") (pin "1") (pinfunction "K_1") (pintype "passive"))
      (node (ref "R18") (pin "1") (pinfunction "1_1") (pintype "passive"))
      (node (ref "R18_a") (pin "1") (pinfunction "1_1") (pintype "passive"))
      (node (ref "U7") (pin "27") (pinfunction "HOA_27") (pintype "output"))
    )
    (net (code "22") (name "/HO_B") (class "Default")
      (node (ref "D4") (pin "1") (pinfunction "K_1") (pintype "passive"))
      (node (ref "R19") (pin "2") (pinfunction "2_2") (pintype "passive"))
      (node (ref "R19_a") (pin "2") (pinfunction "2_2") (pintype "passive"))
      (node (ref "U7") (pin "19") (pinfunction "HOB_19") (pintype "output"))
    )
    (net (code "23") (name "/HS_A") (class "Default")
      (node (ref "C18") (pin "2") (pinfunction "2_2") (pintype "passive"))
      (node (ref "C46") (pin "2") (pinfunction "2_2") (pintype "passive"))
      (node (ref "D12") (pin "1") (pinfunction "K_1") (pintype "passive"))
      (node (ref "D13") (pin "2") (pinfunction "A_2") (pintype "passive"))
      (node (ref "L1") (pin "1") (pinfunction "1_1") (pintype "passive"))
      (node (ref "L10") (pin "1") (pinfunction "1_1") (pintype "passive"))
      (node (ref "L11") (pin "1") (pinfunction "1_1") (pintype "passive"))
      (node (ref "L12") (pin "1") (pinfunction "1_1") (pintype "passive"))
      (node (ref "L13") (pin "1") (pinfunction "1_1") (pintype "passive"))
      (node (ref "L14") (pin "1") (pinfunction "1_1") (pintype "passive"))
      (node (ref "L15") (pin "1") (pinfunction "1_1") (pintype "passive"))
      (node (ref "L16") (pin "1") (pinfunction "1_1") (pintype "passive"))
      (node (ref "L2") (pin "1") (pinfunction "1_1") (pintype "passive"))
      (node (ref "L3") (pin "1") (pinfunction "1_1") (pintype "passive"))
      (node (ref "L4") (pin "1") (pinfunction "1_1") (pintype "passive"))
      (node (ref "L5") (pin "1") (pinfunction "1_1") (pintype "passive"))
      (node (ref "L6") (pin "1") (pinfunction "1_1") (pintype "passive"))
      (node (ref "L7") (pin "1") (pinfunction "1_1") (pintype "passive"))
      (node (ref "L8") (pin "1") (pinfunction "1_1") (pintype "passive"))
      (node (ref "L9") (pin "1") (pinfunction "1_1") (pintype "passive"))
      (node (ref "Q1") (pin "3") (pinfunction "S_3") (pintype "passive"))
      (node (ref "Q3") (pin "2") (pinfunction "D_2") (pintype "passive"))
      (node (ref "R4") (pin "1") (pinfunction "1_1") (pintype "passive"))
      (node (ref "U7") (pin "28") (pinfunction "HSA_28") (pintype "passive"))
    )
    (net (code "24") (name "/HS_B") (class "Default")
      (node (ref "C19") (pin "2") (pinfunction "2_2") (pintype "passive"))
      (node (ref "C54") (pin "2") (pinfunction "2_2") (pintype "passive"))
      (node (ref "D7") (pin "2") (pinfunction "A_2") (pintype "passive"))
      (node (ref "D9") (pin "1") (pinfunction "K_1") (pintype "passive"))
      (node (ref "L1") (pin "2") (pinfunction "2_2") (pintype "passive"))
      (node (ref "L10") (pin "2") (pinfunction "2_2") (pintype "passive"))
      (node (ref "L11") (pin "2") (pinfunction "2_2") (pintype "passive"))
      (node (ref "L12") (pin "2") (pinfunction "2_2") (pintype "passive"))
      (node (ref "L13") (pin "2") (pinfunction "2_2") (pintype "passive"))
      (node (ref "L14") (pin "2") (pinfunction "2_2") (pintype "passive"))
      (node (ref "L15") (pin "2") (pinfunction "2_2") (pintype "passive"))
      (node (ref "L16") (pin "2") (pinfunction "2_2") (pintype "passive"))
      (node (ref "L2") (pin "2") (pinfunction "2_2") (pintype "passive"))
      (node (ref "L3") (pin "2") (pinfunction "2_2") (pintype "passive"))
      (node (ref "L4") (pin "2") (pinfunction "2_2") (pintype "passive"))
      (node (ref "L5") (pin "2") (pinfunction "2_2") (pintype "passive"))
      (node (ref "L6") (pin "2") (pinfunction "2_2") (pintype "passive"))
      (node (ref "L7") (pin "2") (pinfunction "2_2") (pintype "passive"))
      (node (ref "L8") (pin "2") (pinfunction "2_2") (pintype "passive"))
      (node (ref "L9") (pin "2") (pinfunction "2_2") (pintype "passive"))
      (node (ref "Q2") (pin "3") (pinfunction "S_3") (pintype "passive"))
      (node (ref "Q4") (pin "2") (pinfunction "D_2") (pintype "passive"))
      (node (ref "R3") (pin "2") (pinfunction "2_2") (pintype "passive"))
      (node (ref "U7") (pin "18") (pinfunction "HSB_18") (pintype "passive"))
    )
    (net (code "25") (name "/IIN") (class "Default")
      (node (ref "C61") (pin "2") (pinfunction "2_2") (pintype "passive"))
      (node (ref "R56") (pin "2") (pinfunction "2_2") (pintype "passive"))
      (node (ref "U7") (pin "3") (pinfunction "IIN_3") (pintype "output"))
    )
    (net (code "26") (name "/IOUT") (class "Default")
      (node (ref "C62") (pin "2") (pinfunction "2_2") (pintype "passive"))
      (node (ref "R116") (pin "2") (pinfunction "2_2") (pintype "passive"))
      (node (ref "U7") (pin "12") (pinfunction "IOUT_12") (pintype "output"))
    )
    (net (code "27") (name "/LED_A") (class "Default")
      (node (ref "J1") (pin "9") (pinfunction "9_9") (pintype "passive"))
      (node (ref "J2") (pin "11") (pinfunction "11_11") (pintype "passive"))
      (node (ref "R_LEDB_O") (pin "2") (pinfunction "2_2") (pintype "passive"))
    )
    (net (code "28") (name "/LED_B") (class "Default")
      (node (ref "J1") (pin "11") (pinfunction "11_11") (pintype "passive"))
      (node (ref "J2") (pin "9") (pinfunction "9_9") (pintype "passive"))
      (node (ref "R_LEDA_O") (pin "2") (pinfunction "2_2") (pintype "passive"))
    )
    (net (code "29") (name "/LED_VSS") (class "Default")
      (node (ref "Q_LEDA") (pin "2") (pinfunction "S_2") (pintype "passive"))
      (node (ref "Q_LEDB") (pin "2") (pinfunction "S_2") (pintype "passive"))
      (node (ref "Q_LEDVSS") (pin "3") (pinfunction "D_3") (pintype "passive"))
    )
    (net (code "30") (name "/LIA") (class "Default")
      (node (ref "U7") (pin "6") (pinfunction "LIA_6") (pintype "input"))
      (node (ref "U8") (pin "27") (pinfunction "LIA_27") (pintype "output"))
    )
    (net (code "31") (name "/LIB") (class "Default")
      (node (ref "U7") (pin "9") (pinfunction "LIB_9") (pintype "input"))
      (node (ref "U8") (pin "24") (pinfunction "LIB_24") (pintype "output"))
    )
    (net (code "32") (name "/LO_A") (class "Default")
      (node (ref "D5") (pin "1") (pinfunction "K_1") (pintype "passive"))
      (node (ref "R32") (pin "1") (pinfunction "1_1") (pintype "passive"))
      (node (ref "R32_a") (pin "1") (pinfunction "1_1") (pintype "passive"))
      (node (ref "U7") (pin "24") (pinfunction "LOA_24") (pintype "output"))
    )
    (net (code "33") (name "/LO_B") (class "Default")
      (node (ref "D6") (pin "1") (pinfunction "K_1") (pintype "passive"))
      (node (ref "R33") (pin "2") (pinfunction "2_2") (pintype "passive"))
      (node (ref "R33_a") (pin "2") (pinfunction "2_2") (pintype "passive"))
      (node (ref "U7") (pin "22") (pinfunction "LOB_22") (pintype "output"))
    )
    (net (code "34") (name "/NC4") (class "Default")
      (node (ref "C69") (pin "2") (pinfunction "2_2") (pintype "passive"))
      (node (ref "R87_a") (pin "1") (pinfunction "1_1") (pintype "passive"))
      (node (ref "U8") (pin "23") (pinfunction "NC4_23") (pintype "passive"))
    )
    (net (code "35") (name "/OVS") (class "Default")
      (node (ref "R121") (pin "1") (pinfunction "1_1") (pintype "passive"))
      (node (ref "U7") (pin "16") (pinfunction "OVS_16") (pintype "passive"))
    )
    (net (code "36") (name "/PAN_DET") (class "Default")
      (node (ref "D_1A") (pin "1") (pinfunction "K_1") (pintype "passive"))
      (node (ref "D_1B") (pin "1") (pinfunction "K_1") (pintype "passive"))
      (node (ref "Q_LEDVSS") (pin "1") (pinfunction "G_1") (pintype "passive"))
    )
    (net (code "37") (name "/PM") (class "Default")
      (node (ref "U8") (pin "28") (pinfunction "PM_28") (pintype "input"))
    )
    (net (code "38") (name "/RST") (class "Default")
      (node (ref "U7") (pin "10") (pinfunction "PGD_10") (pintype "open_collector"))
    )
    (net (code "39") (name "/SOL_1A") (class "Default")
      (node (ref "D1_a") (pin "2") (pinfunction "A_2") (pintype "passive"))
      (node (ref "D1_b") (pin "2") (pinfunction "A_2") (pintype "passive"))
      (node (ref "D1_c") (pin "2") (pinfunction "A_2") (pintype "passive"))
      (node (ref "D1_d") (pin "2") (pinfunction "A_2") (pintype "passive"))
      (node (ref "D1_e") (pin "2") (pinfunction "A_2") (pintype "passive"))
      (node (ref "D1_f") (pin "2") (pinfunction "A_2") (pintype "passive"))
      (node (ref "D3_a") (pin "1") (pinfunction "K_1") (pintype "passive"))
      (node (ref "D3_b") (pin "1") (pinfunction "K_1") (pintype "passive"))
      (node (ref "D3_c") (pin "1") (pinfunction "K_1") (pintype "passive"))
      (node (ref "D3_d") (pin "1") (pinfunction "K_1") (pintype "passive"))
      (node (ref "D3_e") (pin "1") (pinfunction "K_1") (pintype "passive"))
      (node (ref "D3_f") (pin "1") (pinfunction "K_1") (pintype "passive"))
      (node (ref "J1") (pin "1") (pinfunction "1_1") (pintype "passive"))
      (node (ref "J1") (pin "2") (pinfunction "2_2") (pintype "passive"))
      (node (ref "J1") (pin "3") (pinfunction "3_3") (pintype "passive"))
      (node (ref "J1") (pin "4") (pinfunction "4_4") (pintype "passive"))
      (node (ref "J1") (pin "5") (pinfunction "5_5") (pintype "passive"))
      (node (ref "J1") (pin "6") (pinfunction "6_6") (pintype "passive"))
      (node (ref "J1") (pin "7") (pinfunction "7_7") (pintype "passive"))
      (node (ref "J1") (pin "8") (pinfunction "8_8") (pintype "passive"))
      (node (ref "J_IN") (pin "PLUS") (pinfunction "+_PLUS") (pintype "passive"))
      (node (ref "R_1A_a") (pin "1") (pinfunction "1_1") (pintype "passive"))
    )
    (net (code "40") (name "/SOL_1B") (class "Default")
      (node (ref "D2_a") (pin "2") (pinfunction "A_2") (pintype "passive"))
      (node (ref "D2_b") (pin "2") (pinfunction "A_2") (pintype "passive"))
      (node (ref "D2_c") (pin "2") (pinfunction "A_2") (pintype "passive"))
      (node (ref "D2_d") (pin "2") (pinfunction "A_2") (pintype "passive"))
      (node (ref "D2_e") (pin "2") (pinfunction "A_2") (pintype "passive"))
      (node (ref "D2_f") (pin "2") (pinfunction "A_2") (pintype "passive"))
      (node (ref "D4_a") (pin "1") (pinfunction "K_1") (pintype "passive"))
      (node (ref "D4_b") (pin "1") (pinfunction "K_1") (pintype "passive"))
      (node (ref "D4_c") (pin "1") (pinfunction "K_1") (pintype "passive"))
      (node (ref "D4_d") (pin "1") (pinfunction "K_1") (pintype "passive"))
      (node (ref "D4_e") (pin "1") (pinfunction "K_1") (pintype "passive"))
      (node (ref "D4_f") (pin "1") (pinfunction "K_1") (pintype "passive"))
      (node (ref "J2") (pin "1") (pinfunction "1_1") (pintype "passive"))
      (node (ref "J2") (pin "2") (pinfunction "2_2") (pintype "passive"))
      (node (ref "J2") (pin "3") (pinfunction "3_3") (pintype "passive"))
      (node (ref "J2") (pin "4") (pinfunction "4_4") (pintype "passive"))
      (node (ref "J2") (pin "5") (pinfunction "5_5") (pintype "passive"))
      (node (ref "J2") (pin "6") (pinfunction "6_6") (pintype "passive"))
      (node (ref "J2") (pin "7") (pinfunction "7_7") (pintype "passive"))
      (node (ref "J2") (pin "8") (pinfunction "8_8") (pintype "passive"))
      (node (ref "J_IN") (pin "MINUS") (pinfunction "-_MINUS") (pintype "passive"))
      (node (ref "R_1B_a") (pin "1") (pinfunction "1_1") (pintype "passive"))
    )
    (net (code "41") (name "/VOUT_N") (class "Default")
      (node (ref "J_OUT") (pin "PLUS") (pinfunction "+_PLUS") (pintype "passive"))
      (node (ref "R10") (pin "2") (pinfunction "2_2") (pintype "passive"))
      (node (ref "RA1_N") (pin "1") (pinfunction "1_1") (pintype "passive"))
    )
    (net (code "42") (name "/nRST") (class "Default")
      (node (ref "C66") (pin "2") (pinfunction "2_2") (pintype "passive"))
      (node (ref "R26") (pin "1") (pinfunction "1_1") (pintype "passive"))
      (node (ref "U8") (pin "1") (pinfunction "RST_1") (pintype "input"))
    )
    (net (code "43") (name "10VDC") (class "Default")
      (node (ref "C23_a") (pin "1") (pinfunction "1_1") (pintype "passive"))
      (node (ref "C23_b") (pin "1") (pinfunction "1_1") (pintype "passive"))
      (node (ref "C23_c") (pin "1") (pinfunction "1_1") (pintype "passive"))
      (node (ref "C23_d") (pin "1") (pinfunction "1_1") (pintype "passive"))
      (node (ref "C23_e") (pin "1") (pinfunction "1_1") (pintype "passive"))
      (node (ref "C23_f") (pin "1") (pinfunction "1_1") (pintype "passive"))
      (node (ref "C23_g") (pin "1") (pinfunction "1_1") (pintype "passive"))
      (node (ref "C24") (pin "2") (pinfunction "2_2") (pintype "passive"))
      (node (ref "C31") (pin "1") (pinfunction "1_1") (pintype "passive"))
      (node (ref "C35") (pin "1") (pinfunction "1_1") (pintype "passive"))
      (node (ref "C40") (pin "2") (pinfunction "2_2") (pintype "passive"))
      (node (ref "L0") (pin "2") (pinfunction "2_2") (pintype "passive"))
      (node (ref "R9") (pin "1") (pinfunction "1_1") (pintype "passive"))
      (node (ref "U5V") (pin "1") (pinfunction "VIN_1") (pintype "input"))
      (node (ref "U7") (pin "21") (pinfunction "VCC1_21") (pintype "power_in"))
      (node (ref "U7") (pin "25") (pinfunction "VCC2_25") (pintype "power_in"))
    )
    (net (code "44") (name "AGND") (class "Default")
      (node (ref "C61") (pin "1") (pinfunction "1_1") (pintype "passive"))
      (node (ref "C62") (pin "1") (pinfunction "1_1") (pintype "passive"))
      (node (ref "NT2") (pin "1") (pinfunction "1_1") (pintype "passive"))
      (node (ref "R116") (pin "1") (pinfunction "1_1") (pintype "passive"))
      (node (ref "R56") (pin "1") (pinfunction "1_1") (pintype "passive"))
      (node (ref "U7") (pin "5") (pinfunction "AGND_5") (pintype "power_in"))
      (node (ref "U8") (pin "13") (pinfunction "VSSA_13") (pintype "power_in"))
    )
    (net (code "45") (name "GND") (class "Default")
      (node (ref "C15") (pin "2") (pinfunction "2_2") (pintype "passive"))
      (node (ref "C21") (pin "1") (pinfunction "1_1") (pintype "passive"))
      (node (ref "C22") (pin "1") (pinfunction "1_1") (pintype "passive"))
      (node (ref "C23_a") (pin "2") (pinfunction "2_2") (pintype "passive"))
      (node (ref "C23_b") (pin "2") (pinfunction "2_2") (pintype "passive"))
      (node (ref "C23_c") (pin "2") (pinfunction "2_2") (pintype "passive"))
      (node (ref "C23_d") (pin "2") (pinfunction "2_2") (pintype "passive"))
      (node (ref "C23_e") (pin "2") (pinfunction "2_2") (pintype "passive"))
      (node (ref "C23_f") (pin "2") (pinfunction "2_2") (pintype "passive"))
      (node (ref "C23_g") (pin "2") (pinfunction "2_2") (pintype "passive"))
      (node (ref "C26") (pin "1") (pinfunction "1_1") (pintype "passive"))
      (node (ref "C29") (pin "1") (pinfunction "1_1") (pintype "passive"))
      (node (ref "C31") (pin "2") (pinfunction "2_2") (pintype "passive"))
      (node (ref "C32") (pin "1") (pinfunction "1_1") (pintype "passive"))
      (node (ref "C33") (pin "2") (pinfunction "2_2") (pintype "passive"))
      (node (ref "C34") (pin "1") (pinfunction "1_1") (pintype "passive"))
      (node (ref "C35") (pin "2") (pinfunction "2_2") (pintype "passive"))
      (node (ref "C37") (pin "2") (pinfunction "2_2") (pintype "passive"))
      (node (ref "C38") (pin "1") (pinfunction "1_1") (pintype "passive"))
      (node (ref "C39") (pin "1") (pinfunction "1_1") (pintype "passive"))
      (node (ref "C40") (pin "1") (pinfunction "1_1") (pintype "passive"))
      (node (ref "C42") (pin "1") (pinfunction "1_1") (pintype "passive"))
      (node (ref "C49") (pin "1") (pinfunction "1_1") (pintype "passive"))
      (node (ref "C50") (pin "1") (pinfunction "1_1") (pintype "passive"))
      (node (ref "C51") (pin "1") (pinfunction "1_1") (pintype "passive"))
      (node (ref "C52") (pin "2") (pinfunction "2_2") (pintype "passive"))
      (node (ref "C58") (pin "1") (pinfunction "1_1") (pintype "passive"))
      (node (ref "C59") (pin "1") (pinfunction "1_1") (pintype "passive"))
      (node (ref "C60") (pin "1") (pinfunction "1_1") (pintype "passive"))
      (node (ref "C64") (pin "1") (pinfunction "1_1") (pintype "passive"))
      (node (ref "C66") (pin "1") (pinfunction "1_1") (pintype "passive"))
      (node (ref "C69") (pin "1") (pinfunction "1_1") (pintype "passive"))
      (node (ref "D2") (pin "2") (pinfunction "A_2") (pintype "passive"))
      (node (ref "D_1A_G") (pin "2") (pinfunction "A_2") (pintype "passive"))
      (node (ref "D_1B_G") (pin "2") (pinfunction "A_2") (pintype "passive"))
      (node (ref "NT1") (pin "2") (pinfunction "2_2") (pintype "passive"))
      (node (ref "NT2") (pin "2") (pinfunction "2_2") (pintype "passive"))
      (node (ref "Q_LEDVSS") (pin "2") (pinfunction "S_2") (pintype "passive"))
      (node (ref "R121") (pin "2") (pinfunction "2_2") (pintype "passive"))
      (node (ref "R15") (pin "1") (pinfunction "1_1") (pintype "passive"))
      (node (ref "R20") (pin "2") (pinfunction "2_2") (pintype "passive"))
      (node (ref "R25") (pin "1") (pinfunction "1_1") (pintype "passive"))
      (node (ref "R35") (pin "1") (pinfunction "1_1") (pintype "passive"))
      (node (ref "R38") (pin "1") (pinfunction "1_1") (pintype "passive"))
      (node (ref "R39") (pin "1") (pinfunction "1_1") (pintype "passive"))
      (node (ref "R40") (pin "1") (pinfunction "1_1") (pintype "passive"))
      (node (ref "R41") (pin "1") (pinfunction "1_1") (pintype "passive"))
      (node (ref "R42") (pin "1") (pinfunction "1_1") (pintype "passive"))
      (node (ref "R43") (pin "1") (pinfunction "1_1") (pintype "passive"))
      (node (ref "R53") (pin "2") (pinfunction "2_2") (pintype "passive"))
      (node (ref "R5_a") (pin "1") (pinfunction "1_1") (pintype "passive"))
      (node (ref "R_1A_c") (pin "1") (pinfunction "1_1") (pintype "passive"))
      (node (ref "R_1B_c") (pin "1") (pinfunction "1_1") (pintype "passive"))
      (node (ref "U1") (pin "4") (pinfunction "RTN_4") (pintype "bidirectional"))
      (node (ref "U5V") (pin "2") (pinfunction "GND_2") (pintype "power_in"))
      (node (ref "U7") (pin "23") (pinfunction "PGND_23") (pintype "power_in"))
      (node (ref "U8") (pin "4") (pinfunction "VSSD_4") (pintype "power_in"))
    )
    (net (code "46") (name "GND_IN") (class "Default")
      (node (ref "D3_a") (pin "2") (pinfunction "A_2") (pintype "passive"))
      (node (ref "D3_b") (pin "2") (pinfunction "A_2") (pintype "passive"))
      (node (ref "D3_c") (pin "2") (pinfunction "A_2") (pintype "passive"))
      (node (ref "D3_d") (pin "2") (pinfunction "A_2") (pintype "passive"))
      (node (ref "D3_e") (pin "2") (pinfunction "A_2") (pintype "passive"))
      (node (ref "D3_f") (pin "2") (pinfunction "A_2") (pintype "passive"))
      (node (ref "D4_a") (pin "2") (pinfunction "A_2") (pintype "passive"))
      (node (ref "D4_b") (pin "2") (pinfunction "A_2") (pintype "passive"))
      (node (ref "D4_c") (pin "2") (pinfunction "A_2") (pintype "passive"))
      (node (ref "D4_d") (pin "2") (pinfunction "A_2") (pintype "passive"))
      (node (ref "D4_e") (pin "2") (pinfunction "A_2") (pintype "passive"))
      (node (ref "D4_f") (pin "2") (pinfunction "A_2") (pintype "passive"))
      (node (ref "D_CLAMP_18") (pin "2") (pinfunction "A_2") (pintype "passive"))
      (node (ref "R2") (pin "2") (pinfunction "2_2") (pintype "passive"))
      (node (ref "RB2_N") (pin "1") (pinfunction "1_1") (pintype "passive"))
    )
    (net (code "47") (name "Net-(D2-K)") (class "Default")
      (node (ref "C17") (pin "2") (pinfunction "2_2") (pintype "passive"))
      (node (ref "D2") (pin "1") (pinfunction "K_1") (pintype "passive"))
      (node (ref "L0") (pin "1") (pinfunction "1_1") (pintype "passive"))
      (node (ref "U1") (pin "1") (pinfunction "SW_1") (pintype "bidirectional"))
    )
    (net (code "48") (name "Net-(D3-A)") (class "Default")
      (node (ref "D3") (pin "2") (pinfunction "A_2") (pintype "passive"))
      (node (ref "Q1") (pin "1") (pinfunction "G_1") (pintype "passive"))
      (node (ref "R18") (pin "2") (pinfunction "2_2") (pintype "passive"))
      (node (ref "R18_a") (pin "2") (pinfunction "2_2") (pintype "passive"))
      (node (ref "R4") (pin "2") (pinfunction "2_2") (pintype "passive"))
    )
    (net (code "49") (name "Net-(D4-A)") (class "Default")
      (node (ref "D4") (pin "2") (pinfunction "A_2") (pintype "passive"))
      (node (ref "Q2") (pin "1") (pinfunction "G_1") (pintype "passive"))
      (node (ref "R19") (pin "1") (pinfunction "1_1") (pintype "passive"))
      (node (ref "R19_a") (pin "1") (pinfunction "1_1") (pintype "passive"))
      (node (ref "R3") (pin "1") (pinfunction "1_1") (pintype "passive"))
    )
    (net (code "50") (name "Net-(D5-A)") (class "Default")
      (node (ref "D5") (pin "2") (pinfunction "A_2") (pintype "passive"))
      (node (ref "Q3") (pin "1") (pinfunction "G_1") (pintype "passive"))
      (node (ref "R22") (pin "2") (pinfunction "2_2") (pintype "passive"))
      (node (ref "R32") (pin "2") (pinfunction "2_2") (pintype "passive"))
      (node (ref "R32_a") (pin "2") (pinfunction "2_2") (pintype "passive"))
    )
    (net (code "51") (name "Net-(D6-A)") (class "Default")
      (node (ref "D6") (pin "2") (pinfunction "A_2") (pintype "passive"))
      (node (ref "Q4") (pin "1") (pinfunction "G_1") (pintype "passive"))
      (node (ref "R23") (pin "1") (pinfunction "1_1") (pintype "passive"))
      (node (ref "R33") (pin "1") (pinfunction "1_1") (pintype "passive"))
      (node (ref "R33_a") (pin "1") (pinfunction "1_1") (pintype "passive"))
    )
    (net (code "52") (name "Net-(D14-A)") (class "Default")
      (node (ref "C19") (pin "1") (pinfunction "1_1") (pintype "passive"))
      (node (ref "D14") (pin "2") (pinfunction "A_2") (pintype "passive"))
      (node (ref "R14") (pin "2") (pinfunction "2_2") (pintype "passive"))
    )
    (net (code "53") (name "Net-(D15-A)") (class "Default")
      (node (ref "C18") (pin "1") (pinfunction "1_1") (pintype "passive"))
      (node (ref "D15") (pin "2") (pinfunction "A_2") (pintype "passive"))
      (node (ref "R11") (pin "2") (pinfunction "2_2") (pintype "passive"))
    )
    (net (code "54") (name "Net-(D_CLAMP_1-A)") (class "Default")
      (node (ref "D_CLAMP_1") (pin "2") (pinfunction "A_2") (pintype "passive"))
      (node (ref "D_CLAMP_2") (pin "1") (pinfunction "K_1") (pintype "passive"))
    )
    (net (code "55") (name "Net-(D_CLAMP_2-A)") (class "Default")
      (node (ref "D_CLAMP_2") (pin "2") (pinfunction "A_2") (pintype "passive"))
      (node (ref "D_CLAMP_3") (pin "1") (pinfunction "K_1") (pintype "passive"))
    )
    (net (code "56") (name "Net-(D_CLAMP_3-A)") (class "Default")
      (node (ref "D_CLAMP_3") (pin "2") (pinfunction "A_2") (pintype "passive"))
      (node (ref "D_CLAMP_4") (pin "1") (pinfunction "K_1") (pintype "passive"))
    )
    (net (code "57") (name "Net-(D_CLAMP_4-A)") (class "Default")
      (node (ref "D_CLAMP_4") (pin "2") (pinfunction "A_2") (pintype "passive"))
      (node (ref "D_CLAMP_5") (pin "1") (pinfunction "K_1") (pintype "passive"))
    )
    (net (code "58") (name "Net-(D_CLAMP_5-A)") (class "Default")
      (node (ref "D_CLAMP_5") (pin "2") (pinfunction "A_2") (pintype "passive"))
      (node (ref "D_CLAMP_6") (pin "1") (pinfunction "K_1") (pintype "passive"))
    )
    (net (code "59") (name "Net-(D_CLAMP_6-A)") (class "Default")
      (node (ref "D_CLAMP_6") (pin "2") (pinfunction "A_2") (pintype "passive"))
      (node (ref "D_CLAMP_7") (pin "1") (pinfunction "K_1") (pintype "passive"))
    )
    (net (code "60") (name "Net-(D_CLAMP_7-A)") (class "Default")
      (node (ref "D_CLAMP_7") (pin "2") (pinfunction "A_2") (pintype "passive"))
      (node (ref "D_CLAMP_8") (pin "1") (pinfunction "K_1") (pintype "passive"))
      (node (ref "R16") (pin "2") (pinfunction "2_2") (pintype "passive"))
    )
    (net (code "61") (name "Net-(D_CLAMP_8-A)") (class "Default")
      (node (ref "D_CLAMP_8") (pin "2") (pinfunction "A_2") (pintype "passive"))
      (node (ref "D_CLAMP_9") (pin "1") (pinfunction "K_1") (pintype "passive"))
    )
    (net (code "62") (name "Net-(D_CLAMP_10-A)") (class "Default")
      (node (ref "D_CLAMP_10") (pin "2") (pinfunction "A_2") (pintype "passive"))
      (node (ref "D_CLAMP_11") (pin "1") (pinfunction "K_1") (pintype "passive"))
    )
    (net (code "63") (name "Net-(D_CLAMP_10-K)") (class "Default")
      (node (ref "D_CLAMP_10") (pin "1") (pinfunction "K_1") (pintype "passive"))
      (node (ref "D_CLAMP_9") (pin "2") (pinfunction "A_2") (pintype "passive"))
      (node (ref "R16") (pin "1") (pinfunction "1_1") (pintype "passive"))
    )
    (net (code "64") (name "Net-(D_CLAMP_11-A)") (class "Default")
      (node (ref "D_CLAMP_11") (pin "2") (pinfunction "A_2") (pintype "passive"))
      (node (ref "D_CLAMP_12") (pin "1") (pinfunction "K_1") (pintype "passive"))
    )
    (net (code "65") (name "Net-(D_CLAMP_12-A)") (class "Default")
      (node (ref "D_CLAMP_12") (pin "2") (pinfunction "A_2") (pintype "passive"))
      (node (ref "D_CLAMP_13") (pin "1") (pinfunction "K_1") (pintype "passive"))
    )
    (net (code "66") (name "Net-(D_CLAMP_13-A)") (class "Default")
      (node (ref "D_CLAMP_13") (pin "2") (pinfunction "A_2") (pintype "passive"))
      (node (ref "D_CLAMP_14") (pin "1") (pinfunction "K_1") (pintype "passive"))
    )
    (net (code "67") (name "Net-(D_CLAMP_14-A)") (class "Default")
      (node (ref "D_CLAMP_14") (pin "2") (pinfunction "A_2") (pintype "passive"))
      (node (ref "D_CLAMP_15") (pin "1") (pinfunction "K_1") (pintype "passive"))
    )
    (net (code "68") (name "Net-(D_CLAMP_15-A)") (class "Default")
      (node (ref "D_CLAMP_15") (pin "2") (pinfunction "A_2") (pintype "passive"))
      (node (ref "D_CLAMP_16") (pin "1") (pinfunction "K_1") (pintype "passive"))
    )
    (net (code "69") (name "Net-(D_CLAMP_16-A)") (class "Default")
      (node (ref "D_CLAMP_16") (pin "2") (pinfunction "A_2") (pintype "passive"))
      (node (ref "D_CLAMP_17") (pin "1") (pinfunction "K_1") (pintype "passive"))
    )
    (net (code "70") (name "Net-(D_CLAMP_17-A)") (class "Default")
      (node (ref "D_CLAMP_17") (pin "2") (pinfunction "A_2") (pintype "passive"))
      (node (ref "D_CLAMP_18") (pin "1") (pinfunction "K_1") (pintype "passive"))
    )
    (net (code "71") (name "Net-(J1-Pad10)") (class "Default")
      (node (ref "J1") (pin "10") (pinfunction "10_10") (pintype "passive"))
      (node (ref "R101") (pin "2") (pinfunction "2_2") (pintype "passive"))
    )
    (net (code "72") (name "Net-(J1-Pad12)") (class "Default")
      (node (ref "J1") (pin "12") (pinfunction "12_12") (pintype "passive"))
      (node (ref "R100") (pin "2") (pinfunction "2_2") (pintype "passive"))
    )
    (net (code "73") (name "Net-(J1-SHIELD-PadS1)") (class "Default")
      (node (ref "J1") (pin "S1") (pinfunction "SHIELD_S1") (pintype "passive"))
      (node (ref "J1") (pin "S2") (pinfunction "SHIELD_S2") (pintype "passive"))
    )
    (net (code "74") (name "Net-(J2-Pad10)") (class "Default")
      (node (ref "J2") (pin "10") (pinfunction "10_10") (pintype "passive"))
      (node (ref "R102") (pin "2") (pinfunction "2_2") (pintype "passive"))
    )
    (net (code "75") (name "Net-(J2-Pad12)") (class "Default")
      (node (ref "J2") (pin "12") (pinfunction "12_12") (pintype "passive"))
      (node (ref "R103") (pin "2") (pinfunction "2_2") (pintype "passive"))
    )
    (net (code "76") (name "Net-(J2-SHIELD-PadS1)") (class "Default")
      (node (ref "J2") (pin "S1") (pinfunction "SHIELD_S1") (pintype "passive"))
      (node (ref "J2") (pin "S2") (pinfunction "SHIELD_S2") (pintype "passive"))
    )
    (net (code "77") (name "Net-(Q_LEDA-D)") (class "Default")
      (node (ref "Q_LEDA") (pin "3") (pinfunction "D_3") (pintype "passive"))
      (node (ref "Q_LEDB") (pin "1") (pinfunction "G_1") (pintype "passive"))
      (node (ref "R_LEDB_O") (pin "1") (pinfunction "1_1") (pintype "passive"))
    )
    (net (code "78") (name "Net-(Q_LEDB-D)") (class "Default")
      (node (ref "Q_LEDB") (pin "3") (pinfunction "D_3") (pintype "passive"))
      (node (ref "R_LEDA_O") (pin "1") (pinfunction "1_1") (pintype "passive"))
    )
    (net (code "79") (name "Net-(R5-Pad1)") (class "Default")
      (node (ref "R5") (pin "1") (pinfunction "1_1") (pintype "passive"))
      (node (ref "R5_a") (pin "2") (pinfunction "2_2") (pintype "passive"))
    )
    (net (code "80") (name "Net-(R8-Pad2)") (class "Default")
      (node (ref "R8") (pin "2") (pinfunction "2_2") (pintype "passive"))
      (node (ref "R8_A") (pin "1") (pinfunction "1_1") (pintype "passive"))
    )
    (net (code "81") (name "Net-(R12-Pad2)") (class "Default")
      (node (ref "R12") (pin "2") (pinfunction "2_2") (pintype "passive"))
      (node (ref "R12_A") (pin "1") (pinfunction "1_1") (pintype "passive"))
    )
    (net (code "82") (name "Net-(R24-Pad2)") (class "Default")
      (node (ref "R24") (pin "2") (pinfunction "2_2") (pintype "passive"))
      (node (ref "R24_A") (pin "1") (pinfunction "1_1") (pintype "passive"))
    )
    (net (code "83") (name "Net-(R24_B-Pad1)") (class "Default")
      (node (ref "R24_B") (pin "1") (pinfunction "1_1") (pintype "passive"))
      (node (ref "R34") (pin "2") (pinfunction "2_2") (pintype "passive"))
    )
    (net (code "84") (name "Net-(R_1A_a-Pad2)") (class "Default")
      (node (ref "R_1A_a") (pin "2") (pinfunction "2_2") (pintype "passive"))
      (node (ref "R_1A_b") (pin "1") (pinfunction "1_1") (pintype "passive"))
    )
    (net (code "85") (name "Net-(R_1B_a-Pad2)") (class "Default")
      (node (ref "R_1B_a") (pin "2") (pinfunction "2_2") (pintype "passive"))
      (node (ref "R_1B_b") (pin "1") (pinfunction "1_1") (pintype "passive"))
    )
    (net (code "86") (name "Net-(Ron_a-Pad1)") (class "Default")
      (node (ref "Ron_a") (pin "1") (pinfunction "1_1") (pintype "passive"))
      (node (ref "Ron_b") (pin "1") (pinfunction "1_1") (pintype "passive"))
    )
    (net (code "87") (name "Net-(Ron_b-Pad2)") (class "Default")
      (node (ref "Ron_b") (pin "2") (pinfunction "2_2") (pintype "passive"))
      (node (ref "Ron_c") (pin "2") (pinfunction "2_2") (pintype "passive"))
      (node (ref "Ron_d") (pin "2") (pinfunction "2_2") (pintype "passive"))
    )
    (net (code "88") (name "Net-(U1-BST)") (class "Default")
      (node (ref "C17") (pin "1") (pinfunction "1_1") (pintype "passive"))
      (node (ref "U1") (pin "2") (pinfunction "BST_2") (pintype "bidirectional"))
    )
    (net (code "89") (name "Net-(U1-FB)") (class "Default")
      (node (ref "C24") (pin "1") (pinfunction "1_1") (pintype "passive"))
      (node (ref "R15") (pin "2") (pinfunction "2_2") (pintype "passive"))
      (node (ref "R9") (pin "2") (pinfunction "2_2") (pintype "passive"))
      (node (ref "U1") (pin "5") (pinfunction "FB_5") (pintype "bidirectional"))
    )
    (net (code "90") (name "Net-(U1-RCL)") (class "Default")
      (node (ref "R5") (pin "2") (pinfunction "2_2") (pintype "passive"))
      (node (ref "U1") (pin "3") (pinfunction "RCL_3") (pintype "input"))
    )
    (net (code "91") (name "Net-(U1-RT{slash}SD)") (class "Default")
      (node (ref "Ron_a") (pin "2") (pinfunction "2_2") (pintype "passive"))
      (node (ref "U1") (pin "6") (pinfunction "RT/SD_6") (pintype "input"))
    )
    (net (code "92") (name "Net-(U1-VCC)") (class "Default")
      (node (ref "C15") (pin "1") (pinfunction "1_1") (pintype "passive"))
      (node (ref "U1") (pin "7") (pinfunction "VCC_7") (pintype "power_in"))
    )
    (net (code "93") (name "Net-(U5V-Vout)") (class "Default")
      (node (ref "R17") (pin "1") (pinfunction "1_1") (pintype "passive"))
      (node (ref "U5V") (pin "3") (pinfunction "Vout_3") (pintype "output"))
    )
    (net (code "94") (name "Net-(U7-HBA)") (class "Default")
      (node (ref "C46") (pin "1") (pinfunction "1_1") (pintype "passive"))
      (node (ref "U7") (pin "26") (pinfunction "HBA_26") (pintype "passive"))
    )
    (net (code "95") (name "Net-(U7-HBB)") (class "Default")
      (node (ref "C54") (pin "1") (pinfunction "1_1") (pintype "passive"))
      (node (ref "U7") (pin "20") (pinfunction "HBB_20") (pintype "passive"))
    )
    (net (code "96") (name "Net-(U7-SDA)") (class "Default")
      (node (ref "R8_A") (pin "2") (pinfunction "2_2") (pintype "passive"))
      (node (ref "U7") (pin "2") (pinfunction "SDA_2") (pintype "input"))
    )
    (net (code "97") (name "Net-(U7-SIA)") (class "Default")
      (node (ref "R12_A") (pin "2") (pinfunction "2_2") (pintype "passive"))
      (node (ref "U7") (pin "1") (pinfunction "SIA_1") (pintype "input"))
    )
    (net (code "98") (name "Net-(U7-SIB)") (class "Default")
      (node (ref "R24") (pin "1") (pinfunction "1_1") (pintype "passive"))
      (node (ref "U7") (pin "14") (pinfunction "SIB_14") (pintype "input"))
    )
    (net (code "99") (name "Net-(U7-SOB)") (class "Default")
      (node (ref "R34") (pin "1") (pinfunction "1_1") (pintype "passive"))
      (node (ref "U7") (pin "13") (pinfunction "SOB_13") (pintype "output"))
    )
    (net (code "100") (name "Net-(U8-A0)") (class "Default")
      (node (ref "C49") (pin "2") (pinfunction "2_2") (pintype "passive"))
      (node (ref "R28") (pin "1") (pinfunction "1_1") (pintype "passive"))
      (node (ref "R38") (pin "2") (pinfunction "2_2") (pintype "passive"))
      (node (ref "U8") (pin "14") (pinfunction "A0_14") (pintype "bidirectional"))
    )
    (net (code "101") (name "Net-(U8-A2)") (class "Default")
      (node (ref "C50") (pin "2") (pinfunction "2_2") (pintype "passive"))
      (node (ref "R29") (pin "1") (pinfunction "1_1") (pintype "passive"))
      (node (ref "R39") (pin "2") (pinfunction "2_2") (pintype "passive"))
      (node (ref "U8") (pin "16") (pinfunction "A2_16") (pintype "bidirectional"))
    )
    (net (code "102") (name "Net-(U8-A4)") (class "Default")
      (node (ref "C51") (pin "2") (pinfunction "2_2") (pintype "passive"))
      (node (ref "R30") (pin "2") (pinfunction "2_2") (pintype "passive"))
      (node (ref "R40") (pin "2") (pinfunction "2_2") (pintype "passive"))
      (node (ref "U8") (pin "18") (pinfunction "A4_18") (pintype "bidirectional"))
    )
    (net (code "103") (name "Net-(U8-A6)") (class "Default")
      (node (ref "C52") (pin "1") (pinfunction "1_1") (pintype "passive"))
      (node (ref "R31") (pin "1") (pinfunction "1_1") (pintype "passive"))
      (node (ref "R41") (pin "2") (pinfunction "2_2") (pintype "passive"))
      (node (ref "U8") (pin "20") (pinfunction "A6_20") (pintype "bidirectional"))
    )
    (net (code "104") (name "Net-(U8-I2C0)") (class "Default")
      (node (ref "R36") (pin "2") (pinfunction "2_2") (pintype "passive"))
      (node (ref "U8") (pin "6") (pinfunction "I2C0_6") (pintype "bidirectional"))
    )
    (net (code "105") (name "Net-(U8-I2C1)") (class "Default")
      (node (ref "R42") (pin "2") (pinfunction "2_2") (pintype "passive"))
      (node (ref "U8") (pin "7") (pinfunction "I2C1_7") (pintype "bidirectional"))
    )
    (net (code "106") (name "Net-(U8-I2C2)") (class "Default")
      (node (ref "R43") (pin "2") (pinfunction "2_2") (pintype "passive"))
      (node (ref "U8") (pin "22") (pinfunction "I2C2_22") (pintype "bidirectional"))
    )
    (net (code "107") (name "Net-(U8-NC1)") (class "Default")
      (node (ref "R35") (pin "2") (pinfunction "2_2") (pintype "passive"))
      (node (ref "U8") (pin "2") (pinfunction "NC1_2") (pintype "passive"))
    )
    (net (code "108") (name "Net-(U8-NC2)") (class "Default")
      (node (ref "R45") (pin "2") (pinfunction "2_2") (pintype "passive"))
      (node (ref "U8") (pin "5") (pinfunction "NC2_5") (pintype "passive"))
    )
    (net (code "109") (name "Net-(U8-NC3)") (class "Default")
      (node (ref "R25") (pin "2") (pinfunction "2_2") (pintype "passive"))
      (node (ref "U8") (pin "10") (pinfunction "NC3_10") (pintype "passive"))
    )
    (net (code "110") (name "Net-(U8-VDDA)") (class "Default")
      (node (ref "C33") (pin "1") (pinfunction "1_1") (pintype "passive"))
      (node (ref "C39") (pin "2") (pinfunction "2_2") (pintype "passive"))
      (node (ref "R21") (pin "1") (pinfunction "1_1") (pintype "passive"))
      (node (ref "U8") (pin "12") (pinfunction "VDDA_12") (pintype "power_in"))
    )
    (net (code "111") (name "PGND") (class "Default")
      (node (ref "C1") (pin "1") (pinfunction "1_1") (pintype "passive"))
      (node (ref "C10") (pin "1") (pinfunction "1_1") (pintype "passive"))
      (node (ref "C11") (pin "1") (pinfunction "1_1") (pintype "passive"))
      (node (ref "C12") (pin "1") (pinfunction "1_1") (pintype "passive"))
      (node (ref "C13") (pin "1") (pinfunction "1_1") (pintype "passive"))
      (node (ref "C16") (pin "1") (pinfunction "1_1") (pintype "passive"))
      (node (ref "C20") (pin "1") (pinfunction "1_1") (pintype "passive"))
      (node (ref "C25") (pin "1") (pinfunction "1_1") (pintype "passive"))
      (node (ref "C27") (pin "1") (pinfunction "1_1") (pintype "passive"))
      (node (ref "C28") (pin "1") (pinfunction "1_1") (pintype "passive"))
      (node (ref "C30") (pin "1") (pinfunction "1_1") (pintype "passive"))
      (node (ref "C36") (pin "1") (pinfunction "1_1") (pintype "passive"))
      (node (ref "C4") (pin "1") (pinfunction "1_1") (pintype "passive"))
      (node (ref "C41") (pin "1") (pinfunction "1_1") (pintype "passive"))
      (node (ref "C44") (pin "1") (pinfunction "1_1") (pintype "passive"))
      (node (ref "C45") (pin "1") (pinfunction "1_1") (pintype "passive"))
      (node (ref "C47") (pin "1") (pinfunction "1_1") (pintype "passive"))
      (node (ref "C5") (pin "1") (pinfunction "1_1") (pintype "passive"))
      (node (ref "C6") (pin "1") (pinfunction "1_1") (pintype "passive"))
      (node (ref "C7") (pin "1") (pinfunction "1_1") (pintype "passive"))
      (node (ref "C70") (pin "1") (pinfunction "1_1") (pintype "passive"))
      (node (ref "C72") (pin "1") (pinfunction "1_1") (pintype "passive"))
      (node (ref "C8") (pin "1") (pinfunction "1_1") (pintype "passive"))
      (node (ref "C9") (pin "1") (pinfunction "1_1") (pintype "passive"))
      (node (ref "D12") (pin "2") (pinfunction "A_2") (pintype "passive"))
      (node (ref "D14") (pin "1") (pinfunction "K_1") (pintype "passive"))
      (node (ref "D15") (pin "1") (pinfunction "K_1") (pintype "passive"))
      (node (ref "D9") (pin "2") (pinfunction "A_2") (pintype "passive"))
      (node (ref "NT1") (pin "1") (pinfunction "1_1") (pintype "passive"))
      (node (ref "Q3") (pin "3") (pinfunction "S_3") (pintype "passive"))
      (node (ref "Q4") (pin "3") (pinfunction "S_3") (pintype "passive"))
      (node (ref "R11") (pin "1") (pinfunction "1_1") (pintype "passive"))
      (node (ref "R14") (pin "1") (pinfunction "1_1") (pintype "passive"))
      (node (ref "R2") (pin "1") (pinfunction "1_1") (pintype "passive"))
      (node (ref "R22") (pin "1") (pinfunction "1_1") (pintype "passive"))
      (node (ref "R23") (pin "2") (pinfunction "2_2") (pintype "passive"))
      (node (ref "R6") (pin "1") (pinfunction "1_1") (pintype "passive"))
      (node (ref "RA2_N") (pin "1") (pinfunction "1_1") (pintype "passive"))
      (node (ref "RB2_P") (pin "1") (pinfunction "1_1") (pintype "passive"))
    )
    (net (code "112") (name "VCC_3V3") (class "Default")
      (node (ref "Q_I2C1") (pin "1") (pinfunction "G_1") (pintype "passive"))
      (node (ref "Q_I2C2") (pin "1") (pinfunction "G_1") (pintype "passive"))
      (node (ref "R_SCL3") (pin "2") (pinfunction "2_2") (pintype "passive"))
      (node (ref "R_SDA3") (pin "2") (pinfunction "2_2") (pintype "passive"))
    )
    (net (code "113") (name "VIN_N") (class "Default")
      (node (ref "C1") (pin "2") (pinfunction "2_2") (pintype "passive"))
      (node (ref "C10") (pin "2") (pinfunction "2_2") (pintype "passive"))
      (node (ref "C11") (pin "2") (pinfunction "2_2") (pintype "passive"))
      (node (ref "C12") (pin "2") (pinfunction "2_2") (pintype "passive"))
      (node (ref "C13") (pin "2") (pinfunction "2_2") (pintype "passive"))
      (node (ref "C16") (pin "2") (pinfunction "2_2") (pintype "passive"))
      (node (ref "C20") (pin "2") (pinfunction "2_2") (pintype "passive"))
      (node (ref "C25") (pin "2") (pinfunction "2_2") (pintype "passive"))
      (node (ref "C27") (pin "2") (pinfunction "2_2") (pintype "passive"))
      (node (ref "C28") (pin "2") (pinfunction "2_2") (pintype "passive"))
      (node (ref "C30") (pin "2") (pinfunction "2_2") (pintype "passive"))
      (node (ref "C36") (pin "2") (pinfunction "2_2") (pintype "passive"))
      (node (ref "C4") (pin "2") (pinfunction "2_2") (pintype "passive"))
      (node (ref "C41") (pin "2") (pinfunction "2_2") (pintype "passive"))
      (node (ref "C44") (pin "2") (pinfunction "2_2") (pintype "passive"))
      (node (ref "C45") (pin "2") (pinfunction "2_2") (pintype "passive"))
      (node (ref "C47") (pin "2") (pinfunction "2_2") (pintype "passive"))
      (node (ref "C5") (pin "2") (pinfunction "2_2") (pintype "passive"))
      (node (ref "C6") (pin "2") (pinfunction "2_2") (pintype "passive"))
      (node (ref "C7") (pin "2") (pinfunction "2_2") (pintype "passive"))
      (node (ref "C70") (pin "2") (pinfunction "2_2") (pintype "passive"))
      (node (ref "C72") (pin "2") (pinfunction "2_2") (pintype "passive"))
      (node (ref "C8") (pin "2") (pinfunction "2_2") (pintype "passive"))
      (node (ref "C9") (pin "2") (pinfunction "2_2") (pintype "passive"))
      (node (ref "D13") (pin "1") (pinfunction "K_1") (pintype "passive"))
      (node (ref "Q1") (pin "2") (pinfunction "D_2") (pintype "passive"))
      (node (ref "R1") (pin "1") (pinfunction "1_1") (pintype "passive"))
      (node (ref "R13") (pin "2") (pinfunction "2_2") (pintype "passive"))
      (node (ref "RB1_P") (pin "1") (pinfunction "1_1") (pintype "passive"))
    )
    (net (code "114") (name "VIN_P") (class "Default")
      (node (ref "C21") (pin "2") (pinfunction "2_2") (pintype "passive"))
      (node (ref "C22") (pin "2") (pinfunction "2_2") (pintype "passive"))
      (node (ref "C26") (pin "2") (pinfunction "2_2") (pintype "passive"))
      (node (ref "C64") (pin "2") (pinfunction "2_2") (pintype "passive"))
      (node (ref "D1_a") (pin "1") (pinfunction "K_1") (pintype "passive"))
      (node (ref "D1_b") (pin "1") (pinfunction "K_1") (pintype "passive"))
      (node (ref "D1_c") (pin "1") (pinfunction "K_1") (pintype "passive"))
      (node (ref "D1_d") (pin "1") (pinfunction "K_1") (pintype "passive"))
      (node (ref "D1_e") (pin "1") (pinfunction "K_1") (pintype "passive"))
      (node (ref "D1_f") (pin "1") (pinfunction "K_1") (pintype "passive"))
      (node (ref "D2_a") (pin "1") (pinfunction "K_1") (pintype "passive"))
      (node (ref "D2_b") (pin "1") (pinfunction "K_1") (pintype "passive"))
      (node (ref "D2_c") (pin "1") (pinfunction "K_1") (pintype "passive"))
      (node (ref "D2_d") (pin "1") (pinfunction "K_1") (pintype "passive"))
      (node (ref "D2_e") (pin "1") (pinfunction "K_1") (pintype "passive"))
      (node (ref "D2_f") (pin "1") (pinfunction "K_1") (pintype "passive"))
      (node (ref "D_CLAMP_1") (pin "1") (pinfunction "K_1") (pintype "passive"))
      (node (ref "R1") (pin "2") (pinfunction "2_2") (pintype "passive"))
      (node (ref "RB1_N") (pin "1") (pinfunction "1_1") (pintype "passive"))
      (node (ref "Ron_c") (pin "1") (pinfunction "1_1") (pintype "passive"))
      (node (ref "Ron_d") (pin "1") (pinfunction "1_1") (pintype "passive"))
      (node (ref "U1") (pin "8") (pinfunction "VIN_8") (pintype "input"))
    )
    (net (code "115") (name "VOUT_P") (class "Default")
      (node (ref "D7") (pin "1") (pinfunction "K_1") (pintype "passive"))
      (node (ref "Q2") (pin "2") (pinfunction "D_2") (pintype "passive"))
      (node (ref "R10") (pin "1") (pinfunction "1_1") (pintype "passive"))
      (node (ref "R51") (pin "2") (pinfunction "2_2") (pintype "passive"))
      (node (ref "RA1_P") (pin "1") (pinfunction "1_1") (pintype "passive"))
    )
    (net (code "116") (name "unconnected-(J_IN-PadM)") (class "Default")
      (node (ref "J_IN") (pin "M") (pinfunction "M_M") (pintype "passive"))
    )
    (net (code "117") (name "unconnected-(J_OUT-PadM)") (class "Default")
      (node (ref "J_OUT") (pin "M") (pinfunction "M_M") (pintype "passive"))
    )
    (net (code "118") (name "unconnected-(U7-OVP-Pad15)") (class "Default")
      (node (ref "U7") (pin "15") (pinfunction "OVP_15") (pintype "passive"))
    )
    (net (code "119") (name "unconnected-(U8-PM_OUT-Pad11)") (class "Default")
      (node (ref "U8") (pin "11") (pinfunction "PM_OUT_11") (pintype "output"))
    )
  )
)
